# Protoboard_MX3-11-8.net
KiCad netlist of a schematic drawn in EAGLE
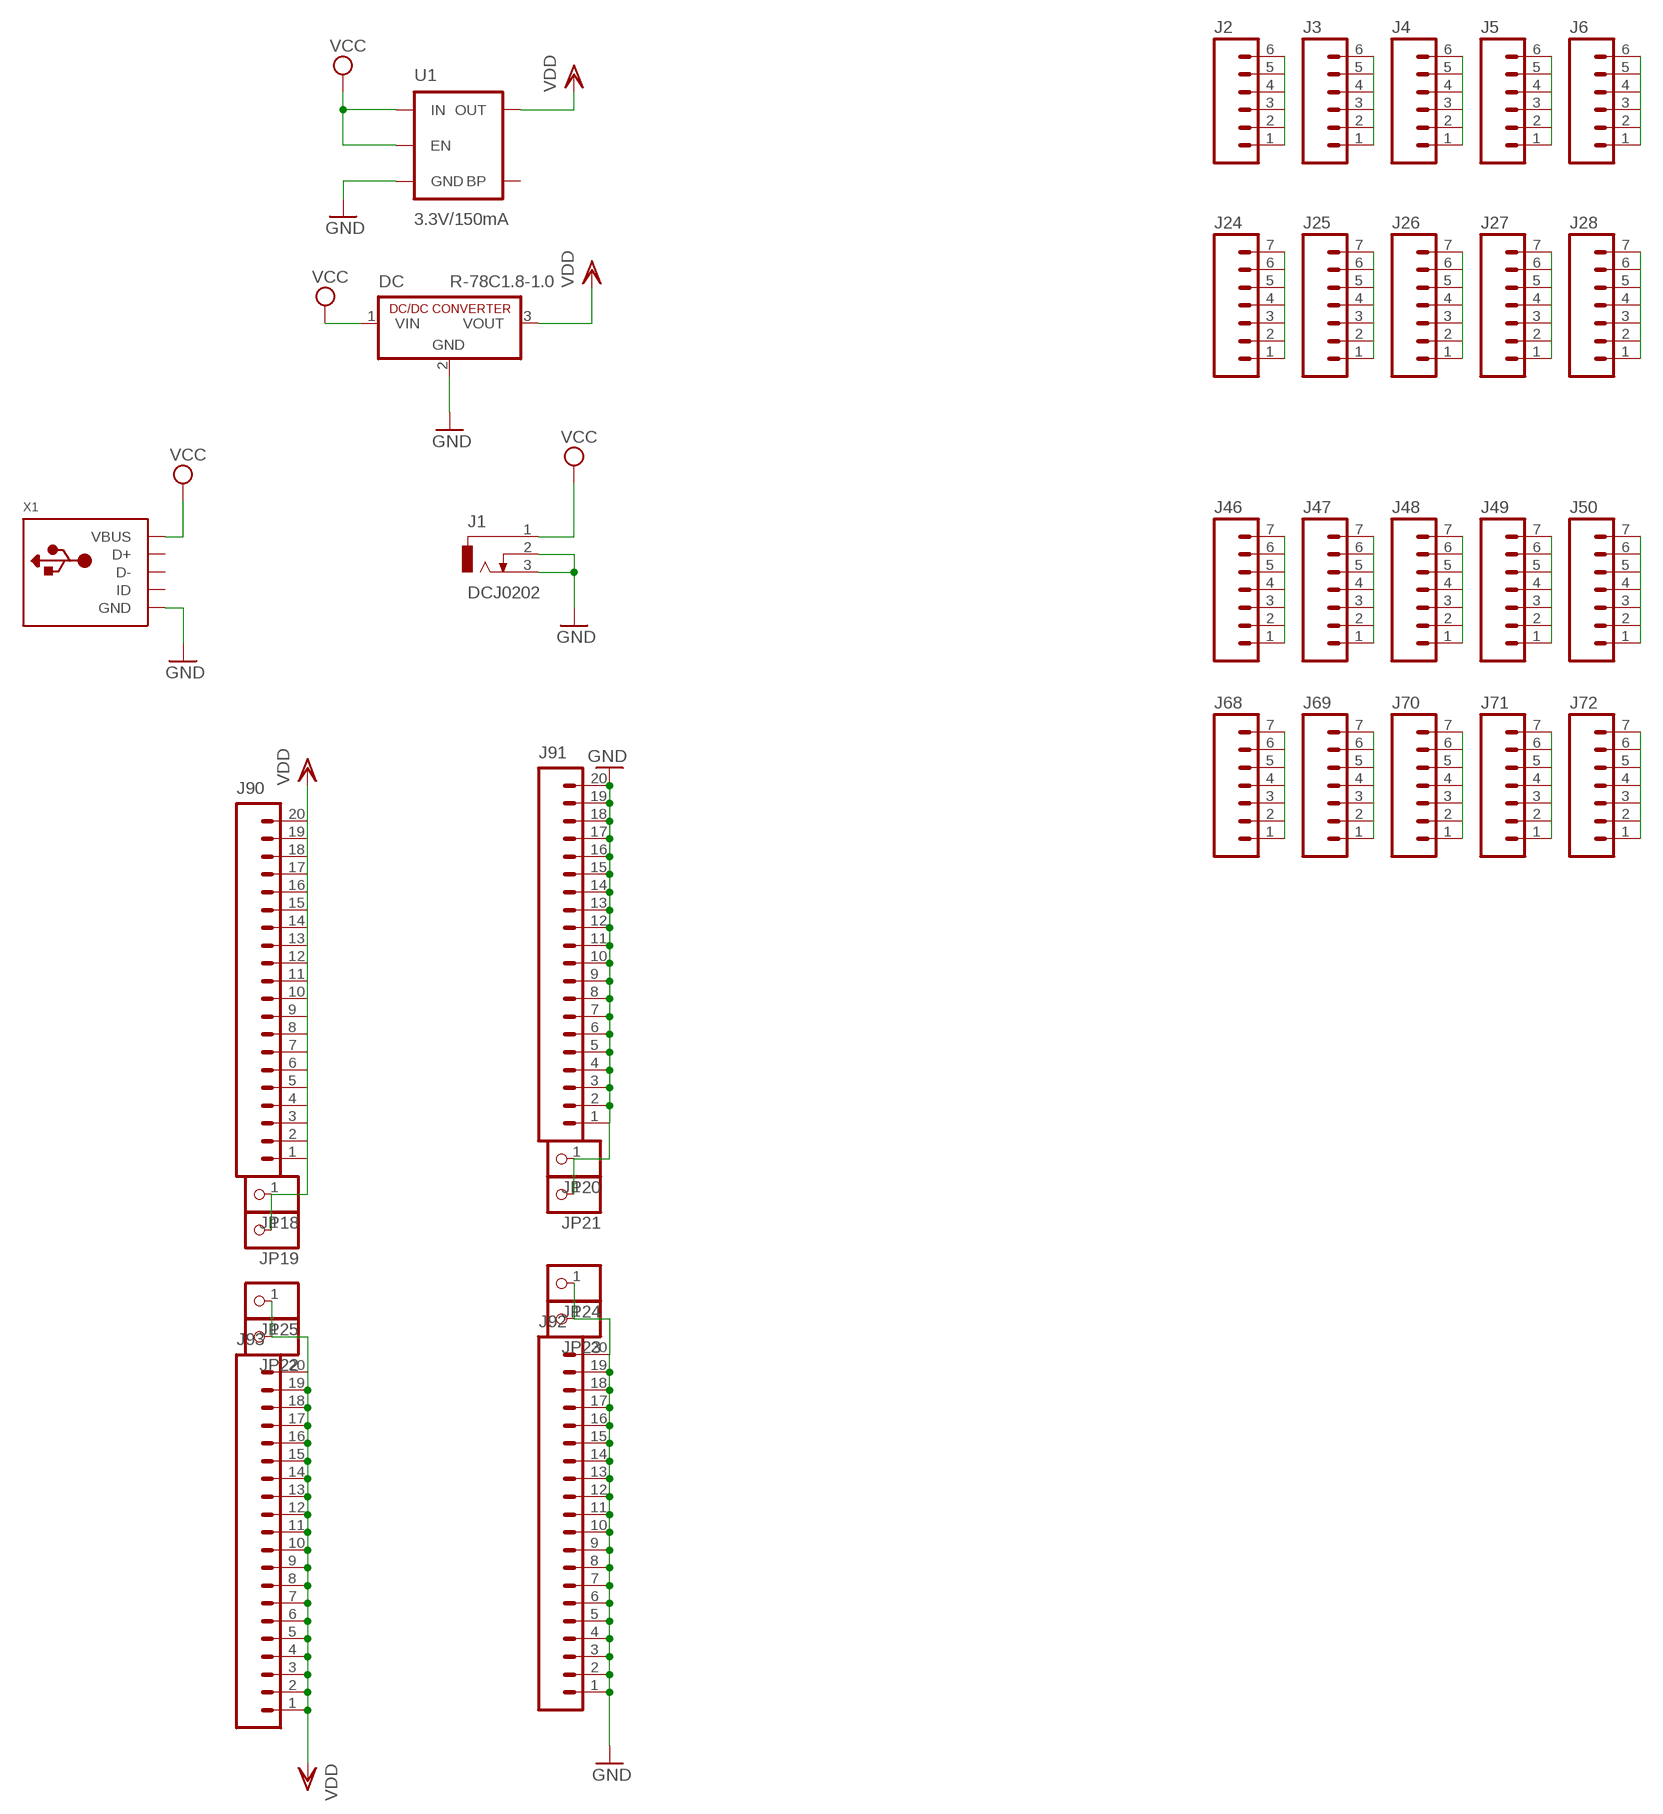
[diagram p0: schematic, sheet 1, part 1 of 2]
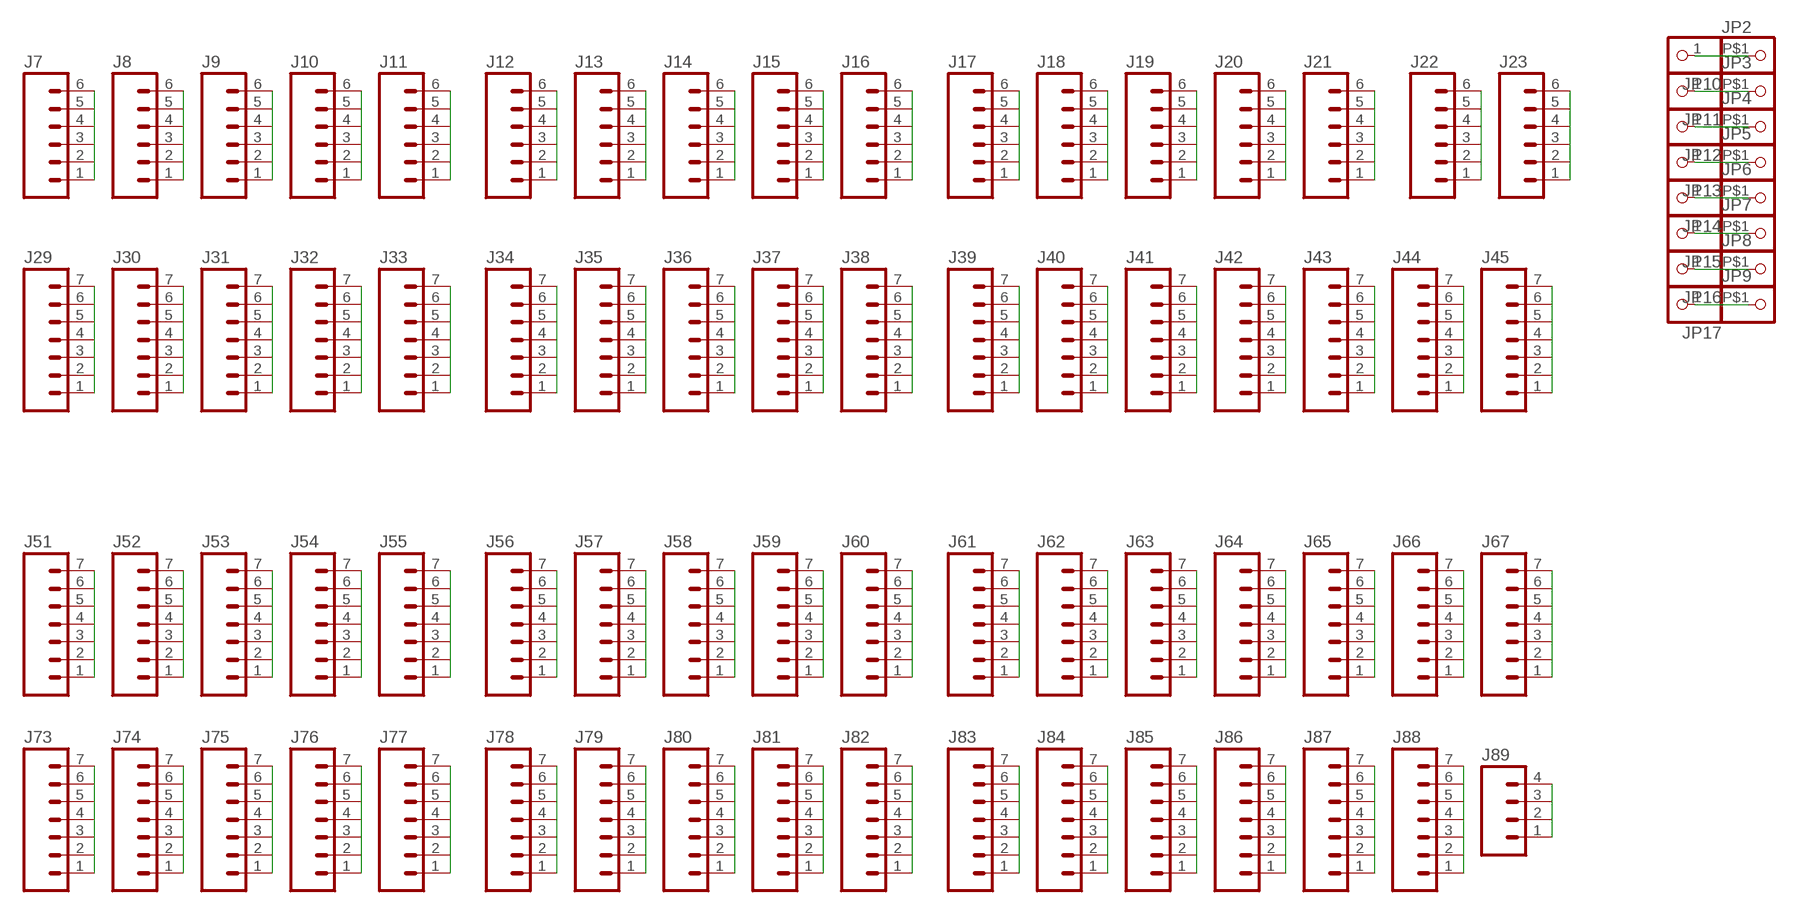
[diagram p1: schematic, sheet 1, part 2 of 2]

(export (version "E")
  (design (tool "Eeschema 10.0.6"))
  (components
    (comp (ref "DC")
      (value "R-78C1.8-1.0")
      (footprint "eagle-import:SIP3")
      (libsource (lib "eagle-import") (part "R-78C-1.01.8"))
    )
    (comp (ref "J1")
      (value "DCJ0202")
      (footprint "eagle-import:DCJ0202")
      (libsource (lib "eagle-import") (part "DCJ0202"))
    )
    (comp (ref "J2")
      (value "M06NO_SILK_FEMALE_PTH")
      (footprint "eagle-import:1X06_NO_SILK")
      (libsource (lib "eagle-import") (part "M06NO_SILK_FEMALE_PTH"))
    )
    (comp (ref "J3")
      (value "M06NO_SILK_FEMALE_PTH")
      (footprint "eagle-import:1X06_NO_SILK")
      (libsource (lib "eagle-import") (part "M06NO_SILK_FEMALE_PTH"))
    )
    (comp (ref "J4")
      (value "M06NO_SILK_FEMALE_PTH")
      (footprint "eagle-import:1X06_NO_SILK")
      (libsource (lib "eagle-import") (part "M06NO_SILK_FEMALE_PTH"))
    )
    (comp (ref "J5")
      (value "M06NO_SILK_FEMALE_PTH")
      (footprint "eagle-import:1X06_NO_SILK")
      (libsource (lib "eagle-import") (part "M06NO_SILK_FEMALE_PTH"))
    )
    (comp (ref "J6")
      (value "M06NO_SILK_FEMALE_PTH")
      (footprint "eagle-import:1X06_NO_SILK")
      (libsource (lib "eagle-import") (part "M06NO_SILK_FEMALE_PTH"))
    )
    (comp (ref "J7")
      (value "M06NO_SILK_FEMALE_PTH")
      (footprint "eagle-import:1X06_NO_SILK")
      (libsource (lib "eagle-import") (part "M06NO_SILK_FEMALE_PTH"))
    )
    (comp (ref "J8")
      (value "M06NO_SILK_FEMALE_PTH")
      (footprint "eagle-import:1X06_NO_SILK")
      (libsource (lib "eagle-import") (part "M06NO_SILK_FEMALE_PTH"))
    )
    (comp (ref "J9")
      (value "M06NO_SILK_FEMALE_PTH")
      (footprint "eagle-import:1X06_NO_SILK")
      (libsource (lib "eagle-import") (part "M06NO_SILK_FEMALE_PTH"))
    )
    (comp (ref "J10")
      (value "M06NO_SILK_FEMALE_PTH")
      (footprint "eagle-import:1X06_NO_SILK")
      (libsource (lib "eagle-import") (part "M06NO_SILK_FEMALE_PTH"))
    )
    (comp (ref "J11")
      (value "M06NO_SILK_FEMALE_PTH")
      (footprint "eagle-import:1X06_NO_SILK")
      (libsource (lib "eagle-import") (part "M06NO_SILK_FEMALE_PTH"))
    )
    (comp (ref "J12")
      (value "M06NO_SILK_FEMALE_PTH")
      (footprint "eagle-import:1X06_NO_SILK")
      (libsource (lib "eagle-import") (part "M06NO_SILK_FEMALE_PTH"))
    )
    (comp (ref "J13")
      (value "M06NO_SILK_FEMALE_PTH")
      (footprint "eagle-import:1X06_NO_SILK")
      (libsource (lib "eagle-import") (part "M06NO_SILK_FEMALE_PTH"))
    )
    (comp (ref "J14")
      (value "M06NO_SILK_FEMALE_PTH")
      (footprint "eagle-import:1X06_NO_SILK")
      (libsource (lib "eagle-import") (part "M06NO_SILK_FEMALE_PTH"))
    )
    (comp (ref "J15")
      (value "M06NO_SILK_FEMALE_PTH")
      (footprint "eagle-import:1X06_NO_SILK")
      (libsource (lib "eagle-import") (part "M06NO_SILK_FEMALE_PTH"))
    )
    (comp (ref "J16")
      (value "M06NO_SILK_FEMALE_PTH")
      (footprint "eagle-import:1X06_NO_SILK")
      (libsource (lib "eagle-import") (part "M06NO_SILK_FEMALE_PTH"))
    )
    (comp (ref "J17")
      (value "M06NO_SILK_FEMALE_PTH")
      (footprint "eagle-import:1X06_NO_SILK")
      (libsource (lib "eagle-import") (part "M06NO_SILK_FEMALE_PTH"))
    )
    (comp (ref "J18")
      (value "M06NO_SILK_FEMALE_PTH")
      (footprint "eagle-import:1X06_NO_SILK")
      (libsource (lib "eagle-import") (part "M06NO_SILK_FEMALE_PTH"))
    )
    (comp (ref "J19")
      (value "M06NO_SILK_FEMALE_PTH")
      (footprint "eagle-import:1X06_NO_SILK")
      (libsource (lib "eagle-import") (part "M06NO_SILK_FEMALE_PTH"))
    )
    (comp (ref "J20")
      (value "M06NO_SILK_FEMALE_PTH")
      (footprint "eagle-import:1X06_NO_SILK")
      (libsource (lib "eagle-import") (part "M06NO_SILK_FEMALE_PTH"))
    )
    (comp (ref "J21")
      (value "M06NO_SILK_FEMALE_PTH")
      (footprint "eagle-import:1X06_NO_SILK")
      (libsource (lib "eagle-import") (part "M06NO_SILK_FEMALE_PTH"))
    )
    (comp (ref "J22")
      (value "M06NO_SILK_FEMALE_PTH")
      (footprint "eagle-import:1X06_NO_SILK")
      (libsource (lib "eagle-import") (part "M06NO_SILK_FEMALE_PTH"))
    )
    (comp (ref "J23")
      (value "M06NO_SILK_FEMALE_PTH")
      (footprint "eagle-import:1X06_NO_SILK")
      (libsource (lib "eagle-import") (part "M06NO_SILK_FEMALE_PTH"))
    )
    (comp (ref "J24")
      (value "M07NO_SILK")
      (footprint "eagle-import:1X07_NO_SILK")
      (libsource (lib "eagle-import") (part "M07NO_SILK"))
    )
    (comp (ref "J25")
      (value "M07NO_SILK")
      (footprint "eagle-import:1X07_NO_SILK")
      (libsource (lib "eagle-import") (part "M07NO_SILK"))
    )
    (comp (ref "J26")
      (value "M07NO_SILK")
      (footprint "eagle-import:1X07_NO_SILK")
      (libsource (lib "eagle-import") (part "M07NO_SILK"))
    )
    (comp (ref "J27")
      (value "M07NO_SILK")
      (footprint "eagle-import:1X07_NO_SILK")
      (libsource (lib "eagle-import") (part "M07NO_SILK"))
    )
    (comp (ref "J28")
      (value "M07NO_SILK")
      (footprint "eagle-import:1X07_NO_SILK")
      (libsource (lib "eagle-import") (part "M07NO_SILK"))
    )
    (comp (ref "J29")
      (value "M07NO_SILK")
      (footprint "eagle-import:1X07_NO_SILK")
      (libsource (lib "eagle-import") (part "M07NO_SILK"))
    )
    (comp (ref "J30")
      (value "M07NO_SILK")
      (footprint "eagle-import:1X07_NO_SILK")
      (libsource (lib "eagle-import") (part "M07NO_SILK"))
    )
    (comp (ref "J31")
      (value "M07NO_SILK")
      (footprint "eagle-import:1X07_NO_SILK")
      (libsource (lib "eagle-import") (part "M07NO_SILK"))
    )
    (comp (ref "J32")
      (value "M07NO_SILK")
      (footprint "eagle-import:1X07_NO_SILK")
      (libsource (lib "eagle-import") (part "M07NO_SILK"))
    )
    (comp (ref "J33")
      (value "M07NO_SILK")
      (footprint "eagle-import:1X07_NO_SILK")
      (libsource (lib "eagle-import") (part "M07NO_SILK"))
    )
    (comp (ref "J34")
      (value "M07NO_SILK")
      (footprint "eagle-import:1X07_NO_SILK")
      (libsource (lib "eagle-import") (part "M07NO_SILK"))
    )
    (comp (ref "J35")
      (value "M07NO_SILK")
      (footprint "eagle-import:1X07_NO_SILK")
      (libsource (lib "eagle-import") (part "M07NO_SILK"))
    )
    (comp (ref "J36")
      (value "M07NO_SILK")
      (footprint "eagle-import:1X07_NO_SILK")
      (libsource (lib "eagle-import") (part "M07NO_SILK"))
    )
    (comp (ref "J37")
      (value "M07NO_SILK")
      (footprint "eagle-import:1X07_NO_SILK")
      (libsource (lib "eagle-import") (part "M07NO_SILK"))
    )
    (comp (ref "J38")
      (value "M07NO_SILK")
      (footprint "eagle-import:1X07_NO_SILK")
      (libsource (lib "eagle-import") (part "M07NO_SILK"))
    )
    (comp (ref "J39")
      (value "M07NO_SILK")
      (footprint "eagle-import:1X07_NO_SILK")
      (libsource (lib "eagle-import") (part "M07NO_SILK"))
    )
    (comp (ref "J40")
      (value "M07NO_SILK")
      (footprint "eagle-import:1X07_NO_SILK")
      (libsource (lib "eagle-import") (part "M07NO_SILK"))
    )
    (comp (ref "J41")
      (value "M07NO_SILK")
      (footprint "eagle-import:1X07_NO_SILK")
      (libsource (lib "eagle-import") (part "M07NO_SILK"))
    )
    (comp (ref "J42")
      (value "M07NO_SILK")
      (footprint "eagle-import:1X07_NO_SILK")
      (libsource (lib "eagle-import") (part "M07NO_SILK"))
    )
    (comp (ref "J43")
      (value "M07NO_SILK")
      (footprint "eagle-import:1X07_NO_SILK")
      (libsource (lib "eagle-import") (part "M07NO_SILK"))
    )
    (comp (ref "J44")
      (value "M07NO_SILK")
      (footprint "eagle-import:1X07_NO_SILK")
      (libsource (lib "eagle-import") (part "M07NO_SILK"))
    )
    (comp (ref "J45")
      (value "M07NO_SILK")
      (footprint "eagle-import:1X07_NO_SILK")
      (libsource (lib "eagle-import") (part "M07NO_SILK"))
    )
    (comp (ref "J46")
      (value "M07NO_SILK")
      (footprint "eagle-import:1X07_NO_SILK")
      (libsource (lib "eagle-import") (part "M07NO_SILK"))
    )
    (comp (ref "J47")
      (value "M07NO_SILK")
      (footprint "eagle-import:1X07_NO_SILK")
      (libsource (lib "eagle-import") (part "M07NO_SILK"))
    )
    (comp (ref "J48")
      (value "M07NO_SILK")
      (footprint "eagle-import:1X07_NO_SILK")
      (libsource (lib "eagle-import") (part "M07NO_SILK"))
    )
    (comp (ref "J49")
      (value "M07NO_SILK")
      (footprint "eagle-import:1X07_NO_SILK")
      (libsource (lib "eagle-import") (part "M07NO_SILK"))
    )
    (comp (ref "J50")
      (value "M07NO_SILK")
      (footprint "eagle-import:1X07_NO_SILK")
      (libsource (lib "eagle-import") (part "M07NO_SILK"))
    )
    (comp (ref "J51")
      (value "M07NO_SILK")
      (footprint "eagle-import:1X07_NO_SILK")
      (libsource (lib "eagle-import") (part "M07NO_SILK"))
    )
    (comp (ref "J52")
      (value "M07NO_SILK")
      (footprint "eagle-import:1X07_NO_SILK")
      (libsource (lib "eagle-import") (part "M07NO_SILK"))
    )
    (comp (ref "J53")
      (value "M07NO_SILK")
      (footprint "eagle-import:1X07_NO_SILK")
      (libsource (lib "eagle-import") (part "M07NO_SILK"))
    )
    (comp (ref "J54")
      (value "M07NO_SILK")
      (footprint "eagle-import:1X07_NO_SILK")
      (libsource (lib "eagle-import") (part "M07NO_SILK"))
    )
    (comp (ref "J55")
      (value "M07NO_SILK")
      (footprint "eagle-import:1X07_NO_SILK")
      (libsource (lib "eagle-import") (part "M07NO_SILK"))
    )
    (comp (ref "J56")
      (value "M07NO_SILK")
      (footprint "eagle-import:1X07_NO_SILK")
      (libsource (lib "eagle-import") (part "M07NO_SILK"))
    )
    (comp (ref "J57")
      (value "M07NO_SILK")
      (footprint "eagle-import:1X07_NO_SILK")
      (libsource (lib "eagle-import") (part "M07NO_SILK"))
    )
    (comp (ref "J58")
      (value "M07NO_SILK")
      (footprint "eagle-import:1X07_NO_SILK")
      (libsource (lib "eagle-import") (part "M07NO_SILK"))
    )
    (comp (ref "J59")
      (value "M07NO_SILK")
      (footprint "eagle-import:1X07_NO_SILK")
      (libsource (lib "eagle-import") (part "M07NO_SILK"))
    )
    (comp (ref "J60")
      (value "M07NO_SILK")
      (footprint "eagle-import:1X07_NO_SILK")
      (libsource (lib "eagle-import") (part "M07NO_SILK"))
    )
    (comp (ref "J61")
      (value "M07NO_SILK")
      (footprint "eagle-import:1X07_NO_SILK")
      (libsource (lib "eagle-import") (part "M07NO_SILK"))
    )
    (comp (ref "J62")
      (value "M07NO_SILK")
      (footprint "eagle-import:1X07_NO_SILK")
      (libsource (lib "eagle-import") (part "M07NO_SILK"))
    )
    (comp (ref "J63")
      (value "M07NO_SILK")
      (footprint "eagle-import:1X07_NO_SILK")
      (libsource (lib "eagle-import") (part "M07NO_SILK"))
    )
    (comp (ref "J64")
      (value "M07NO_SILK")
      (footprint "eagle-import:1X07_NO_SILK")
      (libsource (lib "eagle-import") (part "M07NO_SILK"))
    )
    (comp (ref "J65")
      (value "M07NO_SILK")
      (footprint "eagle-import:1X07_NO_SILK")
      (libsource (lib "eagle-import") (part "M07NO_SILK"))
    )
    (comp (ref "J66")
      (value "M07NO_SILK")
      (footprint "eagle-import:1X07_NO_SILK")
      (libsource (lib "eagle-import") (part "M07NO_SILK"))
    )
    (comp (ref "J67")
      (value "M07NO_SILK")
      (footprint "eagle-import:1X07_NO_SILK")
      (libsource (lib "eagle-import") (part "M07NO_SILK"))
    )
    (comp (ref "J68")
      (value "M07NO_SILK")
      (footprint "eagle-import:1X07_NO_SILK")
      (libsource (lib "eagle-import") (part "M07NO_SILK"))
    )
    (comp (ref "J69")
      (value "M07NO_SILK")
      (footprint "eagle-import:1X07_NO_SILK")
      (libsource (lib "eagle-import") (part "M07NO_SILK"))
    )
    (comp (ref "J70")
      (value "M07NO_SILK")
      (footprint "eagle-import:1X07_NO_SILK")
      (libsource (lib "eagle-import") (part "M07NO_SILK"))
    )
    (comp (ref "J71")
      (value "M07NO_SILK")
      (footprint "eagle-import:1X07_NO_SILK")
      (libsource (lib "eagle-import") (part "M07NO_SILK"))
    )
    (comp (ref "J72")
      (value "M07NO_SILK")
      (footprint "eagle-import:1X07_NO_SILK")
      (libsource (lib "eagle-import") (part "M07NO_SILK"))
    )
    (comp (ref "J73")
      (value "M07NO_SILK")
      (footprint "eagle-import:1X07_NO_SILK")
      (libsource (lib "eagle-import") (part "M07NO_SILK"))
    )
    (comp (ref "J74")
      (value "M07NO_SILK")
      (footprint "eagle-import:1X07_NO_SILK")
      (libsource (lib "eagle-import") (part "M07NO_SILK"))
    )
    (comp (ref "J75")
      (value "M07NO_SILK")
      (footprint "eagle-import:1X07_NO_SILK")
      (libsource (lib "eagle-import") (part "M07NO_SILK"))
    )
    (comp (ref "J76")
      (value "M07NO_SILK")
      (footprint "eagle-import:1X07_NO_SILK")
      (libsource (lib "eagle-import") (part "M07NO_SILK"))
    )
    (comp (ref "J77")
      (value "M07NO_SILK")
      (footprint "eagle-import:1X07_NO_SILK")
      (libsource (lib "eagle-import") (part "M07NO_SILK"))
    )
    (comp (ref "J78")
      (value "M07NO_SILK")
      (footprint "eagle-import:1X07_NO_SILK")
      (libsource (lib "eagle-import") (part "M07NO_SILK"))
    )
    (comp (ref "J79")
      (value "M07NO_SILK")
      (footprint "eagle-import:1X07_NO_SILK")
      (libsource (lib "eagle-import") (part "M07NO_SILK"))
    )
    (comp (ref "J80")
      (value "M07NO_SILK")
      (footprint "eagle-import:1X07_NO_SILK")
      (libsource (lib "eagle-import") (part "M07NO_SILK"))
    )
    (comp (ref "J81")
      (value "M07NO_SILK")
      (footprint "eagle-import:1X07_NO_SILK")
      (libsource (lib "eagle-import") (part "M07NO_SILK"))
    )
    (comp (ref "J82")
      (value "M07NO_SILK")
      (footprint "eagle-import:1X07_NO_SILK")
      (libsource (lib "eagle-import") (part "M07NO_SILK"))
    )
    (comp (ref "J83")
      (value "M07NO_SILK")
      (footprint "eagle-import:1X07_NO_SILK")
      (libsource (lib "eagle-import") (part "M07NO_SILK"))
    )
    (comp (ref "J84")
      (value "M07NO_SILK")
      (footprint "eagle-import:1X07_NO_SILK")
      (libsource (lib "eagle-import") (part "M07NO_SILK"))
    )
    (comp (ref "J85")
      (value "M07NO_SILK")
      (footprint "eagle-import:1X07_NO_SILK")
      (libsource (lib "eagle-import") (part "M07NO_SILK"))
    )
    (comp (ref "J86")
      (value "M07NO_SILK")
      (footprint "eagle-import:1X07_NO_SILK")
      (libsource (lib "eagle-import") (part "M07NO_SILK"))
    )
    (comp (ref "J87")
      (value "M07NO_SILK")
      (footprint "eagle-import:1X07_NO_SILK")
      (libsource (lib "eagle-import") (part "M07NO_SILK"))
    )
    (comp (ref "J88")
      (value "M07NO_SILK")
      (footprint "eagle-import:1X07_NO_SILK")
      (libsource (lib "eagle-import") (part "M07NO_SILK"))
    )
    (comp (ref "J89")
      (value "M04NO_SILK_ALL_ROUND")
      (footprint "eagle-import:1X04_NO_SILK_ALL_ROUND")
      (libsource (lib "eagle-import") (part "M04NO_SILK_ALL_ROUND"))
    )
    (comp (ref "J90")
      (value "M20NO_SILK_KIT")
      (footprint "eagle-import:1X20_NO_SILK_KIT")
      (libsource (lib "eagle-import") (part "M20NO_SILK_KIT"))
    )
    (comp (ref "J91")
      (value "M20NO_SILK_KIT")
      (footprint "eagle-import:1X20_NO_SILK_KIT")
      (libsource (lib "eagle-import") (part "M20NO_SILK_KIT"))
    )
    (comp (ref "J92")
      (value "M20NO_SILK_KIT")
      (footprint "eagle-import:1X20_NO_SILK_KIT")
      (libsource (lib "eagle-import") (part "M20NO_SILK_KIT"))
    )
    (comp (ref "J93")
      (value "M20NO_SILK_KIT")
      (footprint "eagle-import:1X20_NO_SILK_KIT")
      (libsource (lib "eagle-import") (part "M20NO_SILK_KIT"))
    )
    (comp (ref "JP2")
      (value "PINHD-1X1-BIGPOGO")
      (footprint "eagle-import:1X1-BIGPOGO")
      (libsource (lib "eagle-import") (part "PINHD-1X1-BIGPOGO"))
    )
    (comp (ref "JP3")
      (value "PINHD-1X1-BIGPOGO")
      (footprint "eagle-import:1X1-BIGPOGO")
      (libsource (lib "eagle-import") (part "PINHD-1X1-BIGPOGO"))
    )
    (comp (ref "JP4")
      (value "PINHD-1X1-BIGPOGO")
      (footprint "eagle-import:1X1-BIGPOGO")
      (libsource (lib "eagle-import") (part "PINHD-1X1-BIGPOGO"))
    )
    (comp (ref "JP5")
      (value "PINHD-1X1-BIGPOGO")
      (footprint "eagle-import:1X1-BIGPOGO")
      (libsource (lib "eagle-import") (part "PINHD-1X1-BIGPOGO"))
    )
    (comp (ref "JP6")
      (value "PINHD-1X1-BIGPOGO")
      (footprint "eagle-import:1X1-BIGPOGO")
      (libsource (lib "eagle-import") (part "PINHD-1X1-BIGPOGO"))
    )
    (comp (ref "JP7")
      (value "PINHD-1X1-BIGPOGO")
      (footprint "eagle-import:1X1-BIGPOGO")
      (libsource (lib "eagle-import") (part "PINHD-1X1-BIGPOGO"))
    )
    (comp (ref "JP8")
      (value "PINHD-1X1-BIGPOGO")
      (footprint "eagle-import:1X1-BIGPOGO")
      (libsource (lib "eagle-import") (part "PINHD-1X1-BIGPOGO"))
    )
    (comp (ref "JP9")
      (value "PINHD-1X1-BIGPOGO")
      (footprint "eagle-import:1X1-BIGPOGO")
      (libsource (lib "eagle-import") (part "PINHD-1X1-BIGPOGO"))
    )
    (comp (ref "JP10")
      (value "PINHD-1X1CB")
      (footprint "eagle-import:1X01-CLEANBIG")
      (libsource (lib "eagle-import") (part "PINHD-1X1CB"))
    )
    (comp (ref "JP11")
      (value "PINHD-1X1CB")
      (footprint "eagle-import:1X01-CLEANBIG")
      (libsource (lib "eagle-import") (part "PINHD-1X1CB"))
    )
    (comp (ref "JP12")
      (value "PINHD-1X1CB")
      (footprint "eagle-import:1X01-CLEANBIG")
      (libsource (lib "eagle-import") (part "PINHD-1X1CB"))
    )
    (comp (ref "JP13")
      (value "PINHD-1X1CB")
      (footprint "eagle-import:1X01-CLEANBIG")
      (libsource (lib "eagle-import") (part "PINHD-1X1CB"))
    )
    (comp (ref "JP14")
      (value "PINHD-1X1CB")
      (footprint "eagle-import:1X01-CLEANBIG")
      (libsource (lib "eagle-import") (part "PINHD-1X1CB"))
    )
    (comp (ref "JP15")
      (value "PINHD-1X1CB")
      (footprint "eagle-import:1X01-CLEANBIG")
      (libsource (lib "eagle-import") (part "PINHD-1X1CB"))
    )
    (comp (ref "JP16")
      (value "PINHD-1X1CB")
      (footprint "eagle-import:1X01-CLEANBIG")
      (libsource (lib "eagle-import") (part "PINHD-1X1CB"))
    )
    (comp (ref "JP17")
      (value "PINHD-1X1CB")
      (footprint "eagle-import:1X01-CLEANBIG")
      (libsource (lib "eagle-import") (part "PINHD-1X1CB"))
    )
    (comp (ref "JP18")
      (value "PINHD-1X1CB")
      (footprint "eagle-import:1X01-CLEANBIG")
      (libsource (lib "eagle-import") (part "PINHD-1X1CB"))
    )
    (comp (ref "JP19")
      (value "PINHD-1X1CB")
      (footprint "eagle-import:1X01-CLEANBIG")
      (libsource (lib "eagle-import") (part "PINHD-1X1CB"))
    )
    (comp (ref "JP20")
      (value "PINHD-1X1CB")
      (footprint "eagle-import:1X01-CLEANBIG")
      (libsource (lib "eagle-import") (part "PINHD-1X1CB"))
    )
    (comp (ref "JP21")
      (value "PINHD-1X1CB")
      (footprint "eagle-import:1X01-CLEANBIG")
      (libsource (lib "eagle-import") (part "PINHD-1X1CB"))
    )
    (comp (ref "JP22")
      (value "PINHD-1X1CB")
      (footprint "eagle-import:1X01-CLEANBIG")
      (libsource (lib "eagle-import") (part "PINHD-1X1CB"))
    )
    (comp (ref "JP23")
      (value "PINHD-1X1CB")
      (footprint "eagle-import:1X01-CLEANBIG")
      (libsource (lib "eagle-import") (part "PINHD-1X1CB"))
    )
    (comp (ref "JP24")
      (value "PINHD-1X1CB")
      (footprint "eagle-import:1X01-CLEANBIG")
      (libsource (lib "eagle-import") (part "PINHD-1X1CB"))
    )
    (comp (ref "JP25")
      (value "PINHD-1X1CB")
      (footprint "eagle-import:1X01-CLEANBIG")
      (libsource (lib "eagle-import") (part "PINHD-1X1CB"))
    )
    (comp (ref "U1")
      (value "3.3V/150mA")
      (footprint "eagle-import:SOT23-5")
      (libsource (lib "eagle-import") (part "V_REG_MIC52053.3V"))
    )
    (comp (ref "X1")
      (value "USBMICRO_20329")
      (footprint "eagle-import:4UCONN_20329")
      (libsource (lib "eagle-import") (part "USBMICRO_20329"))
    )
  )
  (nets
    (net (code "1") (name "GND") (class "Default")
      (node (ref "DC") (pin "2") (pinfunction "GND_2") (pintype "passive"))
      (node (ref "J1") (pin "2") (pinfunction "2_2") (pintype "passive"))
      (node (ref "J1") (pin "3") (pinfunction "3_3") (pintype "passive"))
      (node (ref "J91") (pin "1") (pinfunction "1_1") (pintype "passive"))
      (node (ref "J91") (pin "10") (pinfunction "10_10") (pintype "passive"))
      (node (ref "J91") (pin "11") (pinfunction "11_11") (pintype "passive"))
      (node (ref "J91") (pin "12") (pinfunction "12_12") (pintype "passive"))
      (node (ref "J91") (pin "13") (pinfunction "13_13") (pintype "passive"))
      (node (ref "J91") (pin "14") (pinfunction "14_14") (pintype "passive"))
      (node (ref "J91") (pin "15") (pinfunction "15_15") (pintype "passive"))
      (node (ref "J91") (pin "16") (pinfunction "16_16") (pintype "passive"))
      (node (ref "J91") (pin "17") (pinfunction "17_17") (pintype "passive"))
      (node (ref "J91") (pin "18") (pinfunction "18_18") (pintype "passive"))
      (node (ref "J91") (pin "19") (pinfunction "19_19") (pintype "passive"))
      (node (ref "J91") (pin "2") (pinfunction "2_2") (pintype "passive"))
      (node (ref "J91") (pin "20") (pinfunction "20_20") (pintype "passive"))
      (node (ref "J91") (pin "3") (pinfunction "3_3") (pintype "passive"))
      (node (ref "J91") (pin "4") (pinfunction "4_4") (pintype "passive"))
      (node (ref "J91") (pin "5") (pinfunction "5_5") (pintype "passive"))
      (node (ref "J91") (pin "6") (pinfunction "6_6") (pintype "passive"))
      (node (ref "J91") (pin "7") (pinfunction "7_7") (pintype "passive"))
      (node (ref "J91") (pin "8") (pinfunction "8_8") (pintype "passive"))
      (node (ref "J91") (pin "9") (pinfunction "9_9") (pintype "passive"))
      (node (ref "J92") (pin "1") (pinfunction "1_1") (pintype "passive"))
      (node (ref "J92") (pin "10") (pinfunction "10_10") (pintype "passive"))
      (node (ref "J92") (pin "11") (pinfunction "11_11") (pintype "passive"))
      (node (ref "J92") (pin "12") (pinfunction "12_12") (pintype "passive"))
      (node (ref "J92") (pin "13") (pinfunction "13_13") (pintype "passive"))
      (node (ref "J92") (pin "14") (pinfunction "14_14") (pintype "passive"))
      (node (ref "J92") (pin "15") (pinfunction "15_15") (pintype "passive"))
      (node (ref "J92") (pin "16") (pinfunction "16_16") (pintype "passive"))
      (node (ref "J92") (pin "17") (pinfunction "17_17") (pintype "passive"))
      (node (ref "J92") (pin "18") (pinfunction "18_18") (pintype "passive"))
      (node (ref "J92") (pin "19") (pinfunction "19_19") (pintype "passive"))
      (node (ref "J92") (pin "2") (pinfunction "2_2") (pintype "passive"))
      (node (ref "J92") (pin "20") (pinfunction "20_20") (pintype "passive"))
      (node (ref "J92") (pin "3") (pinfunction "3_3") (pintype "passive"))
      (node (ref "J92") (pin "4") (pinfunction "4_4") (pintype "passive"))
      (node (ref "J92") (pin "5") (pinfunction "5_5") (pintype "passive"))
      (node (ref "J92") (pin "6") (pinfunction "6_6") (pintype "passive"))
      (node (ref "J92") (pin "7") (pinfunction "7_7") (pintype "passive"))
      (node (ref "J92") (pin "8") (pinfunction "8_8") (pintype "passive"))
      (node (ref "J92") (pin "9") (pinfunction "9_9") (pintype "passive"))
      (node (ref "JP20") (pin "1") (pinfunction "1_1") (pintype "passive"))
      (node (ref "JP21") (pin "1") (pinfunction "1_1") (pintype "passive"))
      (node (ref "JP23") (pin "1") (pinfunction "1_1") (pintype "passive"))
      (node (ref "JP24") (pin "1") (pinfunction "1_1") (pintype "passive"))
      (node (ref "U1") (pin "2") (pinfunction "GND_2") (pintype "input"))
      (node (ref "X1") (pin "BASE@1") (pinfunction "GND_BASE@1") (pintype "power_in"))
      (node (ref "X1") (pin "BASE@2") (pinfunction "GND_BASE@2") (pintype "power_in"))
      (node (ref "X1") (pin "GND") (pinfunction "GND_GND") (pintype "power_in"))
      (node (ref "X1") (pin "SPRT@1") (pinfunction "GND_SPRT@1") (pintype "power_in"))
      (node (ref "X1") (pin "SPRT@2") (pinfunction "GND_SPRT@2") (pintype "power_in"))
      (node (ref "X1") (pin "SPRT@3") (pinfunction "GND_SPRT@3") (pintype "power_in"))
      (node (ref "X1") (pin "SPRT@4") (pinfunction "GND_SPRT@4") (pintype "power_in"))
    )
    (net (code "2") (name "Net-(J2-Pad1)") (class "Default")
      (node (ref "J2") (pin "1") (pinfunction "1_1") (pintype "passive"))
      (node (ref "J2") (pin "2") (pinfunction "2_2") (pintype "passive"))
      (node (ref "J2") (pin "3") (pinfunction "3_3") (pintype "passive"))
      (node (ref "J2") (pin "4") (pinfunction "4_4") (pintype "passive"))
      (node (ref "J2") (pin "5") (pinfunction "5_5") (pintype "passive"))
      (node (ref "J2") (pin "6") (pinfunction "6_6") (pintype "passive"))
    )
    (net (code "3") (name "Net-(J3-Pad1)") (class "Default")
      (node (ref "J3") (pin "1") (pinfunction "1_1") (pintype "passive"))
      (node (ref "J3") (pin "2") (pinfunction "2_2") (pintype "passive"))
      (node (ref "J3") (pin "3") (pinfunction "3_3") (pintype "passive"))
      (node (ref "J3") (pin "4") (pinfunction "4_4") (pintype "passive"))
      (node (ref "J3") (pin "5") (pinfunction "5_5") (pintype "passive"))
      (node (ref "J3") (pin "6") (pinfunction "6_6") (pintype "passive"))
    )
    (net (code "4") (name "Net-(J4-Pad1)") (class "Default")
      (node (ref "J4") (pin "1") (pinfunction "1_1") (pintype "passive"))
      (node (ref "J4") (pin "2") (pinfunction "2_2") (pintype "passive"))
      (node (ref "J4") (pin "3") (pinfunction "3_3") (pintype "passive"))
      (node (ref "J4") (pin "4") (pinfunction "4_4") (pintype "passive"))
      (node (ref "J4") (pin "5") (pinfunction "5_5") (pintype "passive"))
      (node (ref "J4") (pin "6") (pinfunction "6_6") (pintype "passive"))
    )
    (net (code "5") (name "Net-(J5-Pad1)") (class "Default")
      (node (ref "J5") (pin "1") (pinfunction "1_1") (pintype "passive"))
      (node (ref "J5") (pin "2") (pinfunction "2_2") (pintype "passive"))
      (node (ref "J5") (pin "3") (pinfunction "3_3") (pintype "passive"))
      (node (ref "J5") (pin "4") (pinfunction "4_4") (pintype "passive"))
      (node (ref "J5") (pin "5") (pinfunction "5_5") (pintype "passive"))
      (node (ref "J5") (pin "6") (pinfunction "6_6") (pintype "passive"))
    )
    (net (code "6") (name "Net-(J6-Pad1)") (class "Default")
      (node (ref "J6") (pin "1") (pinfunction "1_1") (pintype "passive"))
      (node (ref "J6") (pin "2") (pinfunction "2_2") (pintype "passive"))
      (node (ref "J6") (pin "3") (pinfunction "3_3") (pintype "passive"))
      (node (ref "J6") (pin "4") (pinfunction "4_4") (pintype "passive"))
      (node (ref "J6") (pin "5") (pinfunction "5_5") (pintype "passive"))
      (node (ref "J6") (pin "6") (pinfunction "6_6") (pintype "passive"))
    )
    (net (code "7") (name "Net-(J7-Pad1)") (class "Default")
      (node (ref "J7") (pin "1") (pinfunction "1_1") (pintype "passive"))
      (node (ref "J7") (pin "2") (pinfunction "2_2") (pintype "passive"))
      (node (ref "J7") (pin "3") (pinfunction "3_3") (pintype "passive"))
      (node (ref "J7") (pin "4") (pinfunction "4_4") (pintype "passive"))
      (node (ref "J7") (pin "5") (pinfunction "5_5") (pintype "passive"))
      (node (ref "J7") (pin "6") (pinfunction "6_6") (pintype "passive"))
    )
    (net (code "8") (name "Net-(J8-Pad1)") (class "Default")
      (node (ref "J8") (pin "1") (pinfunction "1_1") (pintype "passive"))
      (node (ref "J8") (pin "2") (pinfunction "2_2") (pintype "passive"))
      (node (ref "J8") (pin "3") (pinfunction "3_3") (pintype "passive"))
      (node (ref "J8") (pin "4") (pinfunction "4_4") (pintype "passive"))
      (node (ref "J8") (pin "5") (pinfunction "5_5") (pintype "passive"))
      (node (ref "J8") (pin "6") (pinfunction "6_6") (pintype "passive"))
    )
    (net (code "9") (name "Net-(J9-Pad1)") (class "Default")
      (node (ref "J9") (pin "1") (pinfunction "1_1") (pintype "passive"))
      (node (ref "J9") (pin "2") (pinfunction "2_2") (pintype "passive"))
      (node (ref "J9") (pin "3") (pinfunction "3_3") (pintype "passive"))
      (node (ref "J9") (pin "4") (pinfunction "4_4") (pintype "passive"))
      (node (ref "J9") (pin "5") (pinfunction "5_5") (pintype "passive"))
      (node (ref "J9") (pin "6") (pinfunction "6_6") (pintype "passive"))
    )
    (net (code "10") (name "Net-(J10-Pad1)") (class "Default")
      (node (ref "J10") (pin "1") (pinfunction "1_1") (pintype "passive"))
      (node (ref "J10") (pin "2") (pinfunction "2_2") (pintype "passive"))
      (node (ref "J10") (pin "3") (pinfunction "3_3") (pintype "passive"))
      (node (ref "J10") (pin "4") (pinfunction "4_4") (pintype "passive"))
      (node (ref "J10") (pin "5") (pinfunction "5_5") (pintype "passive"))
      (node (ref "J10") (pin "6") (pinfunction "6_6") (pintype "passive"))
    )
    (net (code "11") (name "Net-(J11-Pad1)") (class "Default")
      (node (ref "J11") (pin "1") (pinfunction "1_1") (pintype "passive"))
      (node (ref "J11") (pin "2") (pinfunction "2_2") (pintype "passive"))
      (node (ref "J11") (pin "3") (pinfunction "3_3") (pintype "passive"))
      (node (ref "J11") (pin "4") (pinfunction "4_4") (pintype "passive"))
      (node (ref "J11") (pin "5") (pinfunction "5_5") (pintype "passive"))
      (node (ref "J11") (pin "6") (pinfunction "6_6") (pintype "passive"))
    )
    (net (code "12") (name "Net-(J12-Pad1)") (class "Default")
      (node (ref "J12") (pin "1") (pinfunction "1_1") (pintype "passive"))
      (node (ref "J12") (pin "2") (pinfunction "2_2") (pintype "passive"))
      (node (ref "J12") (pin "3") (pinfunction "3_3") (pintype "passive"))
      (node (ref "J12") (pin "4") (pinfunction "4_4") (pintype "passive"))
      (node (ref "J12") (pin "5") (pinfunction "5_5") (pintype "passive"))
      (node (ref "J12") (pin "6") (pinfunction "6_6") (pintype "passive"))
    )
    (net (code "13") (name "Net-(J13-Pad1)") (class "Default")
      (node (ref "J13") (pin "1") (pinfunction "1_1") (pintype "passive"))
      (node (ref "J13") (pin "2") (pinfunction "2_2") (pintype "passive"))
      (node (ref "J13") (pin "3") (pinfunction "3_3") (pintype "passive"))
      (node (ref "J13") (pin "4") (pinfunction "4_4") (pintype "passive"))
      (node (ref "J13") (pin "5") (pinfunction "5_5") (pintype "passive"))
      (node (ref "J13") (pin "6") (pinfunction "6_6") (pintype "passive"))
    )
    (net (code "14") (name "Net-(J14-Pad1)") (class "Default")
      (node (ref "J14") (pin "1") (pinfunction "1_1") (pintype "passive"))
      (node (ref "J14") (pin "2") (pinfunction "2_2") (pintype "passive"))
      (node (ref "J14") (pin "3") (pinfunction "3_3") (pintype "passive"))
      (node (ref "J14") (pin "4") (pinfunction "4_4") (pintype "passive"))
      (node (ref "J14") (pin "5") (pinfunction "5_5") (pintype "passive"))
      (node (ref "J14") (pin "6") (pinfunction "6_6") (pintype "passive"))
    )
    (net (code "15") (name "Net-(J15-Pad1)") (class "Default")
      (node (ref "J15") (pin "1") (pinfunction "1_1") (pintype "passive"))
      (node (ref "J15") (pin "2") (pinfunction "2_2") (pintype "passive"))
      (node (ref "J15") (pin "3") (pinfunction "3_3") (pintype "passive"))
      (node (ref "J15") (pin "4") (pinfunction "4_4") (pintype "passive"))
      (node (ref "J15") (pin "5") (pinfunction "5_5") (pintype "passive"))
      (node (ref "J15") (pin "6") (pinfunction "6_6") (pintype "passive"))
    )
    (net (code "16") (name "Net-(J16-Pad1)") (class "Default")
      (node (ref "J16") (pin "1") (pinfunction "1_1") (pintype "passive"))
      (node (ref "J16") (pin "2") (pinfunction "2_2") (pintype "passive"))
      (node (ref "J16") (pin "3") (pinfunction "3_3") (pintype "passive"))
      (node (ref "J16") (pin "4") (pinfunction "4_4") (pintype "passive"))
      (node (ref "J16") (pin "5") (pinfunction "5_5") (pintype "passive"))
      (node (ref "J16") (pin "6") (pinfunction "6_6") (pintype "passive"))
    )
    (net (code "17") (name "Net-(J17-Pad1)") (class "Default")
      (node (ref "J17") (pin "1") (pinfunction "1_1") (pintype "passive"))
      (node (ref "J17") (pin "2") (pinfunction "2_2") (pintype "passive"))
      (node (ref "J17") (pin "3") (pinfunction "3_3") (pintype "passive"))
      (node (ref "J17") (pin "4") (pinfunction "4_4") (pintype "passive"))
      (node (ref "J17") (pin "5") (pinfunction "5_5") (pintype "passive"))
      (node (ref "J17") (pin "6") (pinfunction "6_6") (pintype "passive"))
    )
    (net (code "18") (name "Net-(J18-Pad1)") (class "Default")
      (node (ref "J18") (pin "1") (pinfunction "1_1") (pintype "passive"))
      (node (ref "J18") (pin "2") (pinfunction "2_2") (pintype "passive"))
      (node (ref "J18") (pin "3") (pinfunction "3_3") (pintype "passive"))
      (node (ref "J18") (pin "4") (pinfunction "4_4") (pintype "passive"))
      (node (ref "J18") (pin "5") (pinfunction "5_5") (pintype "passive"))
      (node (ref "J18") (pin "6") (pinfunction "6_6") (pintype "passive"))
    )
    (net (code "19") (name "Net-(J19-Pad1)") (class "Default")
      (node (ref "J19") (pin "1") (pinfunction "1_1") (pintype "passive"))
      (node (ref "J19") (pin "2") (pinfunction "2_2") (pintype "passive"))
      (node (ref "J19") (pin "3") (pinfunction "3_3") (pintype "passive"))
      (node (ref "J19") (pin "4") (pinfunction "4_4") (pintype "passive"))
      (node (ref "J19") (pin "5") (pinfunction "5_5") (pintype "passive"))
      (node (ref "J19") (pin "6") (pinfunction "6_6") (pintype "passive"))
    )
    (net (code "20") (name "Net-(J20-Pad1)") (class "Default")
      (node (ref "J20") (pin "1") (pinfunction "1_1") (pintype "passive"))
      (node (ref "J20") (pin "2") (pinfunction "2_2") (pintype "passive"))
      (node (ref "J20") (pin "3") (pinfunction "3_3") (pintype "passive"))
      (node (ref "J20") (pin "4") (pinfunction "4_4") (pintype "passive"))
      (node (ref "J20") (pin "5") (pinfunction "5_5") (pintype "passive"))
      (node (ref "J20") (pin "6") (pinfunction "6_6") (pintype "passive"))
    )
    (net (code "21") (name "Net-(J21-Pad1)") (class "Default")
      (node (ref "J21") (pin "1") (pinfunction "1_1") (pintype "passive"))
      (node (ref "J21") (pin "2") (pinfunction "2_2") (pintype "passive"))
      (node (ref "J21") (pin "3") (pinfunction "3_3") (pintype "passive"))
      (node (ref "J21") (pin "4") (pinfunction "4_4") (pintype "passive"))
      (node (ref "J21") (pin "5") (pinfunction "5_5") (pintype "passive"))
      (node (ref "J21") (pin "6") (pinfunction "6_6") (pintype "passive"))
    )
    (net (code "22") (name "Net-(J22-Pad1)") (class "Default")
      (node (ref "J22") (pin "1") (pinfunction "1_1") (pintype "passive"))
      (node (ref "J22") (pin "2") (pinfunction "2_2") (pintype "passive"))
      (node (ref "J22") (pin "3") (pinfunction "3_3") (pintype "passive"))
      (node (ref "J22") (pin "4") (pinfunction "4_4") (pintype "passive"))
      (node (ref "J22") (pin "5") (pinfunction "5_5") (pintype "passive"))
      (node (ref "J22") (pin "6") (pinfunction "6_6") (pintype "passive"))
    )
    (net (code "23") (name "Net-(J23-Pad1)") (class "Default")
      (node (ref "J23") (pin "1") (pinfunction "1_1") (pintype "passive"))
      (node (ref "J23") (pin "2") (pinfunction "2_2") (pintype "passive"))
      (node (ref "J23") (pin "3") (pinfunction "3_3") (pintype "passive"))
      (node (ref "J23") (pin "4") (pinfunction "4_4") (pintype "passive"))
      (node (ref "J23") (pin "5") (pinfunction "5_5") (pintype "passive"))
      (node (ref "J23") (pin "6") (pinfunction "6_6") (pintype "passive"))
    )
    (net (code "24") (name "Net-(J24-Pad1)") (class "Default")
      (node (ref "J24") (pin "1") (pinfunction "1_1") (pintype "passive"))
      (node (ref "J24") (pin "2") (pinfunction "2_2") (pintype "passive"))
      (node (ref "J24") (pin "3") (pinfunction "3_3") (pintype "passive"))
      (node (ref "J24") (pin "4") (pinfunction "4_4") (pintype "passive"))
      (node (ref "J24") (pin "5") (pinfunction "5_5") (pintype "passive"))
      (node (ref "J24") (pin "6") (pinfunction "6_6") (pintype "passive"))
      (node (ref "J24") (pin "7") (pinfunction "7_7") (pintype "passive"))
    )
    (net (code "25") (name "Net-(J25-Pad1)") (class "Default")
      (node (ref "J25") (pin "1") (pinfunction "1_1") (pintype "passive"))
      (node (ref "J25") (pin "2") (pinfunction "2_2") (pintype "passive"))
      (node (ref "J25") (pin "3") (pinfunction "3_3") (pintype "passive"))
      (node (ref "J25") (pin "4") (pinfunction "4_4") (pintype "passive"))
      (node (ref "J25") (pin "5") (pinfunction "5_5") (pintype "passive"))
      (node (ref "J25") (pin "6") (pinfunction "6_6") (pintype "passive"))
      (node (ref "J25") (pin "7") (pinfunction "7_7") (pintype "passive"))
    )
    (net (code "26") (name "Net-(J26-Pad1)") (class "Default")
      (node (ref "J26") (pin "1") (pinfunction "1_1") (pintype "passive"))
      (node (ref "J26") (pin "2") (pinfunction "2_2") (pintype "passive"))
      (node (ref "J26") (pin "3") (pinfunction "3_3") (pintype "passive"))
      (node (ref "J26") (pin "4") (pinfunction "4_4") (pintype "passive"))
      (node (ref "J26") (pin "5") (pinfunction "5_5") (pintype "passive"))
      (node (ref "J26") (pin "6") (pinfunction "6_6") (pintype "passive"))
      (node (ref "J26") (pin "7") (pinfunction "7_7") (pintype "passive"))
    )
    (net (code "27") (name "Net-(J27-Pad1)") (class "Default")
      (node (ref "J27") (pin "1") (pinfunction "1_1") (pintype "passive"))
      (node (ref "J27") (pin "2") (pinfunction "2_2") (pintype "passive"))
      (node (ref "J27") (pin "3") (pinfunction "3_3") (pintype "passive"))
      (node (ref "J27") (pin "4") (pinfunction "4_4") (pintype "passive"))
      (node (ref "J27") (pin "5") (pinfunction "5_5") (pintype "passive"))
      (node (ref "J27") (pin "6") (pinfunction "6_6") (pintype "passive"))
      (node (ref "J27") (pin "7") (pinfunction "7_7") (pintype "passive"))
    )
    (net (code "28") (name "Net-(J28-Pad1)") (class "Default")
      (node (ref "J28") (pin "1") (pinfunction "1_1") (pintype "passive"))
      (node (ref "J28") (pin "2") (pinfunction "2_2") (pintype "passive"))
      (node (ref "J28") (pin "3") (pinfunction "3_3") (pintype "passive"))
      (node (ref "J28") (pin "4") (pinfunction "4_4") (pintype "passive"))
      (node (ref "J28") (pin "5") (pinfunction "5_5") (pintype "passive"))
      (node (ref "J28") (pin "6") (pinfunction "6_6") (pintype "passive"))
      (node (ref "J28") (pin "7") (pinfunction "7_7") (pintype "passive"))
    )
    (net (code "29") (name "Net-(J29-Pad1)") (class "Default")
      (node (ref "J29") (pin "1") (pinfunction "1_1") (pintype "passive"))
      (node (ref "J29") (pin "2") (pinfunction "2_2") (pintype "passive"))
      (node (ref "J29") (pin "3") (pinfunction "3_3") (pintype "passive"))
      (node (ref "J29") (pin "4") (pinfunction "4_4") (pintype "passive"))
      (node (ref "J29") (pin "5") (pinfunction "5_5") (pintype "passive"))
      (node (ref "J29") (pin "6") (pinfunction "6_6") (pintype "passive"))
      (node (ref "J29") (pin "7") (pinfunction "7_7") (pintype "passive"))
    )
    (net (code "30") (name "Net-(J30-Pad1)") (class "Default")
      (node (ref "J30") (pin "1") (pinfunction "1_1") (pintype "passive"))
      (node (ref "J30") (pin "2") (pinfunction "2_2") (pintype "passive"))
      (node (ref "J30") (pin "3") (pinfunction "3_3") (pintype "passive"))
      (node (ref "J30") (pin "4") (pinfunction "4_4") (pintype "passive"))
      (node (ref "J30") (pin "5") (pinfunction "5_5") (pintype "passive"))
      (node (ref "J30") (pin "6") (pinfunction "6_6") (pintype "passive"))
      (node (ref "J30") (pin "7") (pinfunction "7_7") (pintype "passive"))
    )
    (net (code "31") (name "Net-(J31-Pad1)") (class "Default")
      (node (ref "J31") (pin "1") (pinfunction "1_1") (pintype "passive"))
      (node (ref "J31") (pin "2") (pinfunction "2_2") (pintype "passive"))
      (node (ref "J31") (pin "3") (pinfunction "3_3") (pintype "passive"))
      (node (ref "J31") (pin "4") (pinfunction "4_4") (pintype "passive"))
      (node (ref "J31") (pin "5") (pinfunction "5_5") (pintype "passive"))
      (node (ref "J31") (pin "6") (pinfunction "6_6") (pintype "passive"))
      (node (ref "J31") (pin "7") (pinfunction "7_7") (pintype "passive"))
    )
    (net (code "32") (name "Net-(J32-Pad1)") (class "Default")
      (node (ref "J32") (pin "1") (pinfunction "1_1") (pintype "passive"))
      (node (ref "J32") (pin "2") (pinfunction "2_2") (pintype "passive"))
      (node (ref "J32") (pin "3") (pinfunction "3_3") (pintype "passive"))
      (node (ref "J32") (pin "4") (pinfunction "4_4") (pintype "passive"))
      (node (ref "J32") (pin "5") (pinfunction "5_5") (pintype "passive"))
      (node (ref "J32") (pin "6") (pinfunction "6_6") (pintype "passive"))
      (node (ref "J32") (pin "7") (pinfunction "7_7") (pintype "passive"))
    )
    (net (code "33") (name "Net-(J33-Pad1)") (class "Default")
      (node (ref "J33") (pin "1") (pinfunction "1_1") (pintype "passive"))
      (node (ref "J33") (pin "2") (pinfunction "2_2") (pintype "passive"))
      (node (ref "J33") (pin "3") (pinfunction "3_3") (pintype "passive"))
      (node (ref "J33") (pin "4") (pinfunction "4_4") (pintype "passive"))
      (node (ref "J33") (pin "5") (pinfunction "5_5") (pintype "passive"))
      (node (ref "J33") (pin "6") (pinfunction "6_6") (pintype "passive"))
      (node (ref "J33") (pin "7") (pinfunction "7_7") (pintype "passive"))
    )
    (net (code "34") (name "Net-(J34-Pad1)") (class "Default")
      (node (ref "J34") (pin "1") (pinfunction "1_1") (pintype "passive"))
      (node (ref "J34") (pin "2") (pinfunction "2_2") (pintype "passive"))
      (node (ref "J34") (pin "3") (pinfunction "3_3") (pintype "passive"))
      (node (ref "J34") (pin "4") (pinfunction "4_4") (pintype "passive"))
      (node (ref "J34") (pin "5") (pinfunction "5_5") (pintype "passive"))
      (node (ref "J34") (pin "6") (pinfunction "6_6") (pintype "passive"))
      (node (ref "J34") (pin "7") (pinfunction "7_7") (pintype "passive"))
    )
    (net (code "35") (name "Net-(J35-Pad1)") (class "Default")
      (node (ref "J35") (pin "1") (pinfunction "1_1") (pintype "passive"))
      (node (ref "J35") (pin "2") (pinfunction "2_2") (pintype "passive"))
      (node (ref "J35") (pin "3") (pinfunction "3_3") (pintype "passive"))
      (node (ref "J35") (pin "4") (pinfunction "4_4") (pintype "passive"))
      (node (ref "J35") (pin "5") (pinfunction "5_5") (pintype "passive"))
      (node (ref "J35") (pin "6") (pinfunction "6_6") (pintype "passive"))
      (node (ref "J35") (pin "7") (pinfunction "7_7") (pintype "passive"))
    )
    (net (code "36") (name "Net-(J36-Pad1)") (class "Default")
      (node (ref "J36") (pin "1") (pinfunction "1_1") (pintype "passive"))
      (node (ref "J36") (pin "2") (pinfunction "2_2") (pintype "passive"))
      (node (ref "J36") (pin "3") (pinfunction "3_3") (pintype "passive"))
      (node (ref "J36") (pin "4") (pinfunction "4_4") (pintype "passive"))
      (node (ref "J36") (pin "5") (pinfunction "5_5") (pintype "passive"))
      (node (ref "J36") (pin "6") (pinfunction "6_6") (pintype "passive"))
      (node (ref "J36") (pin "7") (pinfunction "7_7") (pintype "passive"))
    )
    (net (code "37") (name "Net-(J37-Pad1)") (class "Default")
      (node (ref "J37") (pin "1") (pinfunction "1_1") (pintype "passive"))
      (node (ref "J37") (pin "2") (pinfunction "2_2") (pintype "passive"))
      (node (ref "J37") (pin "3") (pinfunction "3_3") (pintype "passive"))
      (node (ref "J37") (pin "4") (pinfunction "4_4") (pintype "passive"))
      (node (ref "J37") (pin "5") (pinfunction "5_5") (pintype "passive"))
      (node (ref "J37") (pin "6") (pinfunction "6_6") (pintype "passive"))
      (node (ref "J37") (pin "7") (pinfunction "7_7") (pintype "passive"))
    )
    (net (code "38") (name "Net-(J38-Pad1)") (class "Default")
      (node (ref "J38") (pin "1") (pinfunction "1_1") (pintype "passive"))
      (node (ref "J38") (pin "2") (pinfunction "2_2") (pintype "passive"))
      (node (ref "J38") (pin "3") (pinfunction "3_3") (pintype "passive"))
      (node (ref "J38") (pin "4") (pinfunction "4_4") (pintype "passive"))
      (node (ref "J38") (pin "5") (pinfunction "5_5") (pintype "passive"))
      (node (ref "J38") (pin "6") (pinfunction "6_6") (pintype "passive"))
      (node (ref "J38") (pin "7") (pinfunction "7_7") (pintype "passive"))
    )
    (net (code "39") (name "Net-(J39-Pad1)") (class "Default")
      (node (ref "J39") (pin "1") (pinfunction "1_1") (pintype "passive"))
      (node (ref "J39") (pin "2") (pinfunction "2_2") (pintype "passive"))
      (node (ref "J39") (pin "3") (pinfunction "3_3") (pintype "passive"))
      (node (ref "J39") (pin "4") (pinfunction "4_4") (pintype "passive"))
      (node (ref "J39") (pin "5") (pinfunction "5_5") (pintype "passive"))
      (node (ref "J39") (pin "6") (pinfunction "6_6") (pintype "passive"))
      (node (ref "J39") (pin "7") (pinfunction "7_7") (pintype "passive"))
    )
    (net (code "40") (name "Net-(J40-Pad1)") (class "Default")
      (node (ref "J40") (pin "1") (pinfunction "1_1") (pintype "passive"))
      (node (ref "J40") (pin "2") (pinfunction "2_2") (pintype "passive"))
      (node (ref "J40") (pin "3") (pinfunction "3_3") (pintype "passive"))
      (node (ref "J40") (pin "4") (pinfunction "4_4") (pintype "passive"))
      (node (ref "J40") (pin "5") (pinfunction "5_5") (pintype "passive"))
      (node (ref "J40") (pin "6") (pinfunction "6_6") (pintype "passive"))
      (node (ref "J40") (pin "7") (pinfunction "7_7") (pintype "passive"))
    )
    (net (code "41") (name "Net-(J41-Pad1)") (class "Default")
      (node (ref "J41") (pin "1") (pinfunction "1_1") (pintype "passive"))
      (node (ref "J41") (pin "2") (pinfunction "2_2") (pintype "passive"))
      (node (ref "J41") (pin "3") (pinfunction "3_3") (pintype "passive"))
      (node (ref "J41") (pin "4") (pinfunction "4_4") (pintype "passive"))
      (node (ref "J41") (pin "5") (pinfunction "5_5") (pintype "passive"))
      (node (ref "J41") (pin "6") (pinfunction "6_6") (pintype "passive"))
      (node (ref "J41") (pin "7") (pinfunction "7_7") (pintype "passive"))
    )
    (net (code "42") (name "Net-(J42-Pad1)") (class "Default")
      (node (ref "J42") (pin "1") (pinfunction "1_1") (pintype "passive"))
      (node (ref "J42") (pin "2") (pinfunction "2_2") (pintype "passive"))
      (node (ref "J42") (pin "3") (pinfunction "3_3") (pintype "passive"))
      (node (ref "J42") (pin "4") (pinfunction "4_4") (pintype "passive"))
      (node (ref "J42") (pin "5") (pinfunction "5_5") (pintype "passive"))
      (node (ref "J42") (pin "6") (pinfunction "6_6") (pintype "passive"))
      (node (ref "J42") (pin "7") (pinfunction "7_7") (pintype "passive"))
    )
    (net (code "43") (name "Net-(J43-Pad1)") (class "Default")
      (node (ref "J43") (pin "1") (pinfunction "1_1") (pintype "passive"))
      (node (ref "J43") (pin "2") (pinfunction "2_2") (pintype "passive"))
      (node (ref "J43") (pin "3") (pinfunction "3_3") (pintype "passive"))
      (node (ref "J43") (pin "4") (pinfunction "4_4") (pintype "passive"))
      (node (ref "J43") (pin "5") (pinfunction "5_5") (pintype "passive"))
      (node (ref "J43") (pin "6") (pinfunction "6_6") (pintype "passive"))
      (node (ref "J43") (pin "7") (pinfunction "7_7") (pintype "passive"))
    )
    (net (code "44") (name "Net-(J44-Pad1)") (class "Default")
      (node (ref "J44") (pin "1") (pinfunction "1_1") (pintype "passive"))
      (node (ref "J44") (pin "2") (pinfunction "2_2") (pintype "passive"))
      (node (ref "J44") (pin "3") (pinfunction "3_3") (pintype "passive"))
      (node (ref "J44") (pin "4") (pinfunction "4_4") (pintype "passive"))
      (node (ref "J44") (pin "5") (pinfunction "5_5") (pintype "passive"))
      (node (ref "J44") (pin "6") (pinfunction "6_6") (pintype "passive"))
      (node (ref "J44") (pin "7") (pinfunction "7_7") (pintype "passive"))
    )
    (net (code "45") (name "Net-(J45-Pad1)") (class "Default")
      (node (ref "J45") (pin "1") (pinfunction "1_1") (pintype "passive"))
      (node (ref "J45") (pin "2") (pinfunction "2_2") (pintype "passive"))
      (node (ref "J45") (pin "3") (pinfunction "3_3") (pintype "passive"))
      (node (ref "J45") (pin "4") (pinfunction "4_4") (pintype "passive"))
      (node (ref "J45") (pin "5") (pinfunction "5_5") (pintype "passive"))
      (node (ref "J45") (pin "6") (pinfunction "6_6") (pintype "passive"))
      (node (ref "J45") (pin "7") (pinfunction "7_7") (pintype "passive"))
    )
    (net (code "46") (name "Net-(J46-Pad1)") (class "Default")
      (node (ref "J46") (pin "1") (pinfunction "1_1") (pintype "passive"))
      (node (ref "J46") (pin "2") (pinfunction "2_2") (pintype "passive"))
      (node (ref "J46") (pin "3") (pinfunction "3_3") (pintype "passive"))
      (node (ref "J46") (pin "4") (pinfunction "4_4") (pintype "passive"))
      (node (ref "J46") (pin "5") (pinfunction "5_5") (pintype "passive"))
      (node (ref "J46") (pin "6") (pinfunction "6_6") (pintype "passive"))
      (node (ref "J46") (pin "7") (pinfunction "7_7") (pintype "passive"))
    )
    (net (code "47") (name "Net-(J47-Pad1)") (class "Default")
      (node (ref "J47") (pin "1") (pinfunction "1_1") (pintype "passive"))
      (node (ref "J47") (pin "2") (pinfunction "2_2") (pintype "passive"))
      (node (ref "J47") (pin "3") (pinfunction "3_3") (pintype "passive"))
      (node (ref "J47") (pin "4") (pinfunction "4_4") (pintype "passive"))
      (node (ref "J47") (pin "5") (pinfunction "5_5") (pintype "passive"))
      (node (ref "J47") (pin "6") (pinfunction "6_6") (pintype "passive"))
      (node (ref "J47") (pin "7") (pinfunction "7_7") (pintype "passive"))
    )
    (net (code "48") (name "Net-(J48-Pad1)") (class "Default")
      (node (ref "J48") (pin "1") (pinfunction "1_1") (pintype "passive"))
      (node (ref "J48") (pin "2") (pinfunction "2_2") (pintype "passive"))
      (node (ref "J48") (pin "3") (pinfunction "3_3") (pintype "passive"))
      (node (ref "J48") (pin "4") (pinfunction "4_4") (pintype "passive"))
      (node (ref "J48") (pin "5") (pinfunction "5_5") (pintype "passive"))
      (node (ref "J48") (pin "6") (pinfunction "6_6") (pintype "passive"))
      (node (ref "J48") (pin "7") (pinfunction "7_7") (pintype "passive"))
    )
    (net (code "49") (name "Net-(J49-Pad1)") (class "Default")
      (node (ref "J49") (pin "1") (pinfunction "1_1") (pintype "passive"))
      (node (ref "J49") (pin "2") (pinfunction "2_2") (pintype "passive"))
      (node (ref "J49") (pin "3") (pinfunction "3_3") (pintype "passive"))
      (node (ref "J49") (pin "4") (pinfunction "4_4") (pintype "passive"))
      (node (ref "J49") (pin "5") (pinfunction "5_5") (pintype "passive"))
      (node (ref "J49") (pin "6") (pinfunction "6_6") (pintype "passive"))
      (node (ref "J49") (pin "7") (pinfunction "7_7") (pintype "passive"))
    )
    (net (code "50") (name "Net-(J50-Pad1)") (class "Default")
      (node (ref "J50") (pin "1") (pinfunction "1_1") (pintype "passive"))
      (node (ref "J50") (pin "2") (pinfunction "2_2") (pintype "passive"))
      (node (ref "J50") (pin "3") (pinfunction "3_3") (pintype "passive"))
      (node (ref "J50") (pin "4") (pinfunction "4_4") (pintype "passive"))
      (node (ref "J50") (pin "5") (pinfunction "5_5") (pintype "passive"))
      (node (ref "J50") (pin "6") (pinfunction "6_6") (pintype "passive"))
      (node (ref "J50") (pin "7") (pinfunction "7_7") (pintype "passive"))
    )
    (net (code "51") (name "Net-(J51-Pad1)") (class "Default")
      (node (ref "J51") (pin "1") (pinfunction "1_1") (pintype "passive"))
      (node (ref "J51") (pin "2") (pinfunction "2_2") (pintype "passive"))
      (node (ref "J51") (pin "3") (pinfunction "3_3") (pintype "passive"))
      (node (ref "J51") (pin "4") (pinfunction "4_4") (pintype "passive"))
      (node (ref "J51") (pin "5") (pinfunction "5_5") (pintype "passive"))
      (node (ref "J51") (pin "6") (pinfunction "6_6") (pintype "passive"))
      (node (ref "J51") (pin "7") (pinfunction "7_7") (pintype "passive"))
    )
    (net (code "52") (name "Net-(J52-Pad1)") (class "Default")
      (node (ref "J52") (pin "1") (pinfunction "1_1") (pintype "passive"))
      (node (ref "J52") (pin "2") (pinfunction "2_2") (pintype "passive"))
      (node (ref "J52") (pin "3") (pinfunction "3_3") (pintype "passive"))
      (node (ref "J52") (pin "4") (pinfunction "4_4") (pintype "passive"))
      (node (ref "J52") (pin "5") (pinfunction "5_5") (pintype "passive"))
      (node (ref "J52") (pin "6") (pinfunction "6_6") (pintype "passive"))
      (node (ref "J52") (pin "7") (pinfunction "7_7") (pintype "passive"))
    )
    (net (code "53") (name "Net-(J53-Pad1)") (class "Default")
      (node (ref "J53") (pin "1") (pinfunction "1_1") (pintype "passive"))
      (node (ref "J53") (pin "2") (pinfunction "2_2") (pintype "passive"))
      (node (ref "J53") (pin "3") (pinfunction "3_3") (pintype "passive"))
      (node (ref "J53") (pin "4") (pinfunction "4_4") (pintype "passive"))
      (node (ref "J53") (pin "5") (pinfunction "5_5") (pintype "passive"))
      (node (ref "J53") (pin "6") (pinfunction "6_6") (pintype "passive"))
      (node (ref "J53") (pin "7") (pinfunction "7_7") (pintype "passive"))
    )
    (net (code "54") (name "Net-(J54-Pad1)") (class "Default")
      (node (ref "J54") (pin "1") (pinfunction "1_1") (pintype "passive"))
      (node (ref "J54") (pin "2") (pinfunction "2_2") (pintype "passive"))
      (node (ref "J54") (pin "3") (pinfunction "3_3") (pintype "passive"))
      (node (ref "J54") (pin "4") (pinfunction "4_4") (pintype "passive"))
      (node (ref "J54") (pin "5") (pinfunction "5_5") (pintype "passive"))
      (node (ref "J54") (pin "6") (pinfunction "6_6") (pintype "passive"))
      (node (ref "J54") (pin "7") (pinfunction "7_7") (pintype "passive"))
    )
    (net (code "55") (name "Net-(J55-Pad1)") (class "Default")
      (node (ref "J55") (pin "1") (pinfunction "1_1") (pintype "passive"))
      (node (ref "J55") (pin "2") (pinfunction "2_2") (pintype "passive"))
      (node (ref "J55") (pin "3") (pinfunction "3_3") (pintype "passive"))
      (node (ref "J55") (pin "4") (pinfunction "4_4") (pintype "passive"))
      (node (ref "J55") (pin "5") (pinfunction "5_5") (pintype "passive"))
      (node (ref "J55") (pin "6") (pinfunction "6_6") (pintype "passive"))
      (node (ref "J55") (pin "7") (pinfunction "7_7") (pintype "passive"))
    )
    (net (code "56") (name "Net-(J56-Pad1)") (class "Default")
      (node (ref "J56") (pin "1") (pinfunction "1_1") (pintype "passive"))
      (node (ref "J56") (pin "2") (pinfunction "2_2") (pintype "passive"))
      (node (ref "J56") (pin "3") (pinfunction "3_3") (pintype "passive"))
      (node (ref "J56") (pin "4") (pinfunction "4_4") (pintype "passive"))
      (node (ref "J56") (pin "5") (pinfunction "5_5") (pintype "passive"))
      (node (ref "J56") (pin "6") (pinfunction "6_6") (pintype "passive"))
      (node (ref "J56") (pin "7") (pinfunction "7_7") (pintype "passive"))
    )
    (net (code "57") (name "Net-(J57-Pad1)") (class "Default")
      (node (ref "J57") (pin "1") (pinfunction "1_1") (pintype "passive"))
      (node (ref "J57") (pin "2") (pinfunction "2_2") (pintype "passive"))
      (node (ref "J57") (pin "3") (pinfunction "3_3") (pintype "passive"))
      (node (ref "J57") (pin "4") (pinfunction "4_4") (pintype "passive"))
      (node (ref "J57") (pin "5") (pinfunction "5_5") (pintype "passive"))
      (node (ref "J57") (pin "6") (pinfunction "6_6") (pintype "passive"))
      (node (ref "J57") (pin "7") (pinfunction "7_7") (pintype "passive"))
    )
    (net (code "58") (name "Net-(J58-Pad1)") (class "Default")
      (node (ref "J58") (pin "1") (pinfunction "1_1") (pintype "passive"))
      (node (ref "J58") (pin "2") (pinfunction "2_2") (pintype "passive"))
      (node (ref "J58") (pin "3") (pinfunction "3_3") (pintype "passive"))
      (node (ref "J58") (pin "4") (pinfunction "4_4") (pintype "passive"))
      (node (ref "J58") (pin "5") (pinfunction "5_5") (pintype "passive"))
      (node (ref "J58") (pin "6") (pinfunction "6_6") (pintype "passive"))
      (node (ref "J58") (pin "7") (pinfunction "7_7") (pintype "passive"))
    )
    (net (code "59") (name "Net-(J59-Pad1)") (class "Default")
      (node (ref "J59") (pin "1") (pinfunction "1_1") (pintype "passive"))
      (node (ref "J59") (pin "2") (pinfunction "2_2") (pintype "passive"))
      (node (ref "J59") (pin "3") (pinfunction "3_3") (pintype "passive"))
      (node (ref "J59") (pin "4") (pinfunction "4_4") (pintype "passive"))
      (node (ref "J59") (pin "5") (pinfunction "5_5") (pintype "passive"))
      (node (ref "J59") (pin "6") (pinfunction "6_6") (pintype "passive"))
      (node (ref "J59") (pin "7") (pinfunction "7_7") (pintype "passive"))
    )
    (net (code "60") (name "Net-(J60-Pad1)") (class "Default")
      (node (ref "J60") (pin "1") (pinfunction "1_1") (pintype "passive"))
      (node (ref "J60") (pin "2") (pinfunction "2_2") (pintype "passive"))
      (node (ref "J60") (pin "3") (pinfunction "3_3") (pintype "passive"))
      (node (ref "J60") (pin "4") (pinfunction "4_4") (pintype "passive"))
      (node (ref "J60") (pin "5") (pinfunction "5_5") (pintype "passive"))
      (node (ref "J60") (pin "6") (pinfunction "6_6") (pintype "passive"))
      (node (ref "J60") (pin "7") (pinfunction "7_7") (pintype "passive"))
    )
    (net (code "61") (name "Net-(J61-Pad1)") (class "Default")
      (node (ref "J61") (pin "1") (pinfunction "1_1") (pintype "passive"))
      (node (ref "J61") (pin "2") (pinfunction "2_2") (pintype "passive"))
      (node (ref "J61") (pin "3") (pinfunction "3_3") (pintype "passive"))
      (node (ref "J61") (pin "4") (pinfunction "4_4") (pintype "passive"))
      (node (ref "J61") (pin "5") (pinfunction "5_5") (pintype "passive"))
      (node (ref "J61") (pin "6") (pinfunction "6_6") (pintype "passive"))
      (node (ref "J61") (pin "7") (pinfunction "7_7") (pintype "passive"))
    )
    (net (code "62") (name "Net-(J62-Pad1)") (class "Default")
      (node (ref "J62") (pin "1") (pinfunction "1_1") (pintype "passive"))
      (node (ref "J62") (pin "2") (pinfunction "2_2") (pintype "passive"))
      (node (ref "J62") (pin "3") (pinfunction "3_3") (pintype "passive"))
      (node (ref "J62") (pin "4") (pinfunction "4_4") (pintype "passive"))
      (node (ref "J62") (pin "5") (pinfunction "5_5") (pintype "passive"))
      (node (ref "J62") (pin "6") (pinfunction "6_6") (pintype "passive"))
      (node (ref "J62") (pin "7") (pinfunction "7_7") (pintype "passive"))
    )
    (net (code "63") (name "Net-(J63-Pad1)") (class "Default")
      (node (ref "J63") (pin "1") (pinfunction "1_1") (pintype "passive"))
      (node (ref "J63") (pin "2") (pinfunction "2_2") (pintype "passive"))
      (node (ref "J63") (pin "3") (pinfunction "3_3") (pintype "passive"))
      (node (ref "J63") (pin "4") (pinfunction "4_4") (pintype "passive"))
      (node (ref "J63") (pin "5") (pinfunction "5_5") (pintype "passive"))
      (node (ref "J63") (pin "6") (pinfunction "6_6") (pintype "passive"))
      (node (ref "J63") (pin "7") (pinfunction "7_7") (pintype "passive"))
    )
    (net (code "64") (name "Net-(J64-Pad1)") (class "Default")
      (node (ref "J64") (pin "1") (pinfunction "1_1") (pintype "passive"))
      (node (ref "J64") (pin "2") (pinfunction "2_2") (pintype "passive"))
      (node (ref "J64") (pin "3") (pinfunction "3_3") (pintype "passive"))
      (node (ref "J64") (pin "4") (pinfunction "4_4") (pintype "passive"))
      (node (ref "J64") (pin "5") (pinfunction "5_5") (pintype "passive"))
      (node (ref "J64") (pin "6") (pinfunction "6_6") (pintype "passive"))
      (node (ref "J64") (pin "7") (pinfunction "7_7") (pintype "passive"))
    )
    (net (code "65") (name "Net-(J65-Pad1)") (class "Default")
      (node (ref "J65") (pin "1") (pinfunction "1_1") (pintype "passive"))
      (node (ref "J65") (pin "2") (pinfunction "2_2") (pintype "passive"))
      (node (ref "J65") (pin "3") (pinfunction "3_3") (pintype "passive"))
      (node (ref "J65") (pin "4") (pinfunction "4_4") (pintype "passive"))
      (node (ref "J65") (pin "5") (pinfunction "5_5") (pintype "passive"))
      (node (ref "J65") (pin "6") (pinfunction "6_6") (pintype "passive"))
      (node (ref "J65") (pin "7") (pinfunction "7_7") (pintype "passive"))
    )
    (net (code "66") (name "Net-(J66-Pad1)") (class "Default")
      (node (ref "J66") (pin "1") (pinfunction "1_1") (pintype "passive"))
      (node (ref "J66") (pin "2") (pinfunction "2_2") (pintype "passive"))
      (node (ref "J66") (pin "3") (pinfunction "3_3") (pintype "passive"))
      (node (ref "J66") (pin "4") (pinfunction "4_4") (pintype "passive"))
      (node (ref "J66") (pin "5") (pinfunction "5_5") (pintype "passive"))
      (node (ref "J66") (pin "6") (pinfunction "6_6") (pintype "passive"))
      (node (ref "J66") (pin "7") (pinfunction "7_7") (pintype "passive"))
    )
    (net (code "67") (name "Net-(J67-Pad1)") (class "Default")
      (node (ref "J67") (pin "1") (pinfunction "1_1") (pintype "passive"))
      (node (ref "J67") (pin "2") (pinfunction "2_2") (pintype "passive"))
      (node (ref "J67") (pin "3") (pinfunction "3_3") (pintype "passive"))
      (node (ref "J67") (pin "4") (pinfunction "4_4") (pintype "passive"))
      (node (ref "J67") (pin "5") (pinfunction "5_5") (pintype "passive"))
      (node (ref "J67") (pin "6") (pinfunction "6_6") (pintype "passive"))
      (node (ref "J67") (pin "7") (pinfunction "7_7") (pintype "passive"))
    )
    (net (code "68") (name "Net-(J68-Pad1)") (class "Default")
      (node (ref "J68") (pin "1") (pinfunction "1_1") (pintype "passive"))
      (node (ref "J68") (pin "2") (pinfunction "2_2") (pintype "passive"))
      (node (ref "J68") (pin "3") (pinfunction "3_3") (pintype "passive"))
      (node (ref "J68") (pin "4") (pinfunction "4_4") (pintype "passive"))
      (node (ref "J68") (pin "5") (pinfunction "5_5") (pintype "passive"))
      (node (ref "J68") (pin "6") (pinfunction "6_6") (pintype "passive"))
      (node (ref "J68") (pin "7") (pinfunction "7_7") (pintype "passive"))
    )
    (net (code "69") (name "Net-(J69-Pad1)") (class "Default")
      (node (ref "J69") (pin "1") (pinfunction "1_1") (pintype "passive"))
      (node (ref "J69") (pin "2") (pinfunction "2_2") (pintype "passive"))
      (node (ref "J69") (pin "3") (pinfunction "3_3") (pintype "passive"))
      (node (ref "J69") (pin "4") (pinfunction "4_4") (pintype "passive"))
      (node (ref "J69") (pin "5") (pinfunction "5_5") (pintype "passive"))
      (node (ref "J69") (pin "6") (pinfunction "6_6") (pintype "passive"))
      (node (ref "J69") (pin "7") (pinfunction "7_7") (pintype "passive"))
    )
    (net (code "70") (name "Net-(J70-Pad1)") (class "Default")
      (node (ref "J70") (pin "1") (pinfunction "1_1") (pintype "passive"))
      (node (ref "J70") (pin "2") (pinfunction "2_2") (pintype "passive"))
      (node (ref "J70") (pin "3") (pinfunction "3_3") (pintype "passive"))
      (node (ref "J70") (pin "4") (pinfunction "4_4") (pintype "passive"))
      (node (ref "J70") (pin "5") (pinfunction "5_5") (pintype "passive"))
      (node (ref "J70") (pin "6") (pinfunction "6_6") (pintype "passive"))
      (node (ref "J70") (pin "7") (pinfunction "7_7") (pintype "passive"))
    )
    (net (code "71") (name "Net-(J71-Pad1)") (class "Default")
      (node (ref "J71") (pin "1") (pinfunction "1_1") (pintype "passive"))
      (node (ref "J71") (pin "2") (pinfunction "2_2") (pintype "passive"))
      (node (ref "J71") (pin "3") (pinfunction "3_3") (pintype "passive"))
      (node (ref "J71") (pin "4") (pinfunction "4_4") (pintype "passive"))
      (node (ref "J71") (pin "5") (pinfunction "5_5") (pintype "passive"))
      (node (ref "J71") (pin "6") (pinfunction "6_6") (pintype "passive"))
      (node (ref "J71") (pin "7") (pinfunction "7_7") (pintype "passive"))
    )
    (net (code "72") (name "Net-(J72-Pad1)") (class "Default")
      (node (ref "J72") (pin "1") (pinfunction "1_1") (pintype "passive"))
      (node (ref "J72") (pin "2") (pinfunction "2_2") (pintype "passive"))
      (node (ref "J72") (pin "3") (pinfunction "3_3") (pintype "passive"))
      (node (ref "J72") (pin "4") (pinfunction "4_4") (pintype "passive"))
      (node (ref "J72") (pin "5") (pinfunction "5_5") (pintype "passive"))
      (node (ref "J72") (pin "6") (pinfunction "6_6") (pintype "passive"))
      (node (ref "J72") (pin "7") (pinfunction "7_7") (pintype "passive"))
    )
    (net (code "73") (name "Net-(J73-Pad1)") (class "Default")
      (node (ref "J73") (pin "1") (pinfunction "1_1") (pintype "passive"))
      (node (ref "J73") (pin "2") (pinfunction "2_2") (pintype "passive"))
      (node (ref "J73") (pin "3") (pinfunction "3_3") (pintype "passive"))
      (node (ref "J73") (pin "4") (pinfunction "4_4") (pintype "passive"))
      (node (ref "J73") (pin "5") (pinfunction "5_5") (pintype "passive"))
      (node (ref "J73") (pin "6") (pinfunction "6_6") (pintype "passive"))
      (node (ref "J73") (pin "7") (pinfunction "7_7") (pintype "passive"))
    )
    (net (code "74") (name "Net-(J74-Pad1)") (class "Default")
      (node (ref "J74") (pin "1") (pinfunction "1_1") (pintype "passive"))
      (node (ref "J74") (pin "2") (pinfunction "2_2") (pintype "passive"))
      (node (ref "J74") (pin "3") (pinfunction "3_3") (pintype "passive"))
      (node (ref "J74") (pin "4") (pinfunction "4_4") (pintype "passive"))
      (node (ref "J74") (pin "5") (pinfunction "5_5") (pintype "passive"))
      (node (ref "J74") (pin "6") (pinfunction "6_6") (pintype "passive"))
      (node (ref "J74") (pin "7") (pinfunction "7_7") (pintype "passive"))
    )
    (net (code "75") (name "Net-(J75-Pad1)") (class "Default")
      (node (ref "J75") (pin "1") (pinfunction "1_1") (pintype "passive"))
      (node (ref "J75") (pin "2") (pinfunction "2_2") (pintype "passive"))
      (node (ref "J75") (pin "3") (pinfunction "3_3") (pintype "passive"))
      (node (ref "J75") (pin "4") (pinfunction "4_4") (pintype "passive"))
      (node (ref "J75") (pin "5") (pinfunction "5_5") (pintype "passive"))
      (node (ref "J75") (pin "6") (pinfunction "6_6") (pintype "passive"))
      (node (ref "J75") (pin "7") (pinfunction "7_7") (pintype "passive"))
    )
    (net (code "76") (name "Net-(J76-Pad1)") (class "Default")
      (node (ref "J76") (pin "1") (pinfunction "1_1") (pintype "passive"))
      (node (ref "J76") (pin "2") (pinfunction "2_2") (pintype "passive"))
      (node (ref "J76") (pin "3") (pinfunction "3_3") (pintype "passive"))
      (node (ref "J76") (pin "4") (pinfunction "4_4") (pintype "passive"))
      (node (ref "J76") (pin "5") (pinfunction "5_5") (pintype "passive"))
      (node (ref "J76") (pin "6") (pinfunction "6_6") (pintype "passive"))
      (node (ref "J76") (pin "7") (pinfunction "7_7") (pintype "passive"))
    )
    (net (code "77") (name "Net-(J77-Pad1)") (class "Default")
      (node (ref "J77") (pin "1") (pinfunction "1_1") (pintype "passive"))
      (node (ref "J77") (pin "2") (pinfunction "2_2") (pintype "passive"))
      (node (ref "J77") (pin "3") (pinfunction "3_3") (pintype "passive"))
      (node (ref "J77") (pin "4") (pinfunction "4_4") (pintype "passive"))
      (node (ref "J77") (pin "5") (pinfunction "5_5") (pintype "passive"))
      (node (ref "J77") (pin "6") (pinfunction "6_6") (pintype "passive"))
      (node (ref "J77") (pin "7") (pinfunction "7_7") (pintype "passive"))
    )
    (net (code "78") (name "Net-(J78-Pad1)") (class "Default")
      (node (ref "J78") (pin "1") (pinfunction "1_1") (pintype "passive"))
      (node (ref "J78") (pin "2") (pinfunction "2_2") (pintype "passive"))
      (node (ref "J78") (pin "3") (pinfunction "3_3") (pintype "passive"))
      (node (ref "J78") (pin "4") (pinfunction "4_4") (pintype "passive"))
      (node (ref "J78") (pin "5") (pinfunction "5_5") (pintype "passive"))
      (node (ref "J78") (pin "6") (pinfunction "6_6") (pintype "passive"))
      (node (ref "J78") (pin "7") (pinfunction "7_7") (pintype "passive"))
    )
    (net (code "79") (name "Net-(J79-Pad1)") (class "Default")
      (node (ref "J79") (pin "1") (pinfunction "1_1") (pintype "passive"))
      (node (ref "J79") (pin "2") (pinfunction "2_2") (pintype "passive"))
      (node (ref "J79") (pin "3") (pinfunction "3_3") (pintype "passive"))
      (node (ref "J79") (pin "4") (pinfunction "4_4") (pintype "passive"))
      (node (ref "J79") (pin "5") (pinfunction "5_5") (pintype "passive"))
      (node (ref "J79") (pin "6") (pinfunction "6_6") (pintype "passive"))
      (node (ref "J79") (pin "7") (pinfunction "7_7") (pintype "passive"))
    )
    (net (code "80") (name "Net-(J80-Pad1)") (class "Default")
      (node (ref "J80") (pin "1") (pinfunction "1_1") (pintype "passive"))
      (node (ref "J80") (pin "2") (pinfunction "2_2") (pintype "passive"))
      (node (ref "J80") (pin "3") (pinfunction "3_3") (pintype "passive"))
      (node (ref "J80") (pin "4") (pinfunction "4_4") (pintype "passive"))
      (node (ref "J80") (pin "5") (pinfunction "5_5") (pintype "passive"))
      (node (ref "J80") (pin "6") (pinfunction "6_6") (pintype "passive"))
      (node (ref "J80") (pin "7") (pinfunction "7_7") (pintype "passive"))
    )
    (net (code "81") (name "Net-(J81-Pad1)") (class "Default")
      (node (ref "J81") (pin "1") (pinfunction "1_1") (pintype "passive"))
      (node (ref "J81") (pin "2") (pinfunction "2_2") (pintype "passive"))
      (node (ref "J81") (pin "3") (pinfunction "3_3") (pintype "passive"))
      (node (ref "J81") (pin "4") (pinfunction "4_4") (pintype "passive"))
      (node (ref "J81") (pin "5") (pinfunction "5_5") (pintype "passive"))
      (node (ref "J81") (pin "6") (pinfunction "6_6") (pintype "passive"))
      (node (ref "J81") (pin "7") (pinfunction "7_7") (pintype "passive"))
    )
    (net (code "82") (name "Net-(J82-Pad1)") (class "Default")
      (node (ref "J82") (pin "1") (pinfunction "1_1") (pintype "passive"))
      (node (ref "J82") (pin "2") (pinfunction "2_2") (pintype "passive"))
      (node (ref "J82") (pin "3") (pinfunction "3_3") (pintype "passive"))
      (node (ref "J82") (pin "4") (pinfunction "4_4") (pintype "passive"))
      (node (ref "J82") (pin "5") (pinfunction "5_5") (pintype "passive"))
      (node (ref "J82") (pin "6") (pinfunction "6_6") (pintype "passive"))
      (node (ref "J82") (pin "7") (pinfunction "7_7") (pintype "passive"))
    )
    (net (code "83") (name "Net-(J83-Pad1)") (class "Default")
      (node (ref "J83") (pin "1") (pinfunction "1_1") (pintype "passive"))
      (node (ref "J83") (pin "2") (pinfunction "2_2") (pintype "passive"))
      (node (ref "J83") (pin "3") (pinfunction "3_3") (pintype "passive"))
      (node (ref "J83") (pin "4") (pinfunction "4_4") (pintype "passive"))
      (node (ref "J83") (pin "5") (pinfunction "5_5") (pintype "passive"))
      (node (ref "J83") (pin "6") (pinfunction "6_6") (pintype "passive"))
      (node (ref "J83") (pin "7") (pinfunction "7_7") (pintype "passive"))
    )
    (net (code "84") (name "Net-(J84-Pad1)") (class "Default")
      (node (ref "J84") (pin "1") (pinfunction "1_1") (pintype "passive"))
      (node (ref "J84") (pin "2") (pinfunction "2_2") (pintype "passive"))
      (node (ref "J84") (pin "3") (pinfunction "3_3") (pintype "passive"))
      (node (ref "J84") (pin "4") (pinfunction "4_4") (pintype "passive"))
      (node (ref "J84") (pin "5") (pinfunction "5_5") (pintype "passive"))
      (node (ref "J84") (pin "6") (pinfunction "6_6") (pintype "passive"))
      (node (ref "J84") (pin "7") (pinfunction "7_7") (pintype "passive"))
    )
    (net (code "85") (name "Net-(J85-Pad1)") (class "Default")
      (node (ref "J85") (pin "1") (pinfunction "1_1") (pintype "passive"))
      (node (ref "J85") (pin "2") (pinfunction "2_2") (pintype "passive"))
      (node (ref "J85") (pin "3") (pinfunction "3_3") (pintype "passive"))
      (node (ref "J85") (pin "4") (pinfunction "4_4") (pintype "passive"))
      (node (ref "J85") (pin "5") (pinfunction "5_5") (pintype "passive"))
      (node (ref "J85") (pin "6") (pinfunction "6_6") (pintype "passive"))
      (node (ref "J85") (pin "7") (pinfunction "7_7") (pintype "passive"))
    )
    (net (code "86") (name "Net-(J86-Pad1)") (class "Default")
      (node (ref "J86") (pin "1") (pinfunction "1_1") (pintype "passive"))
      (node (ref "J86") (pin "2") (pinfunction "2_2") (pintype "passive"))
      (node (ref "J86") (pin "3") (pinfunction "3_3") (pintype "passive"))
      (node (ref "J86") (pin "4") (pinfunction "4_4") (pintype "passive"))
      (node (ref "J86") (pin "5") (pinfunction "5_5") (pintype "passive"))
      (node (ref "J86") (pin "6") (pinfunction "6_6") (pintype "passive"))
      (node (ref "J86") (pin "7") (pinfunction "7_7") (pintype "passive"))
    )
    (net (code "87") (name "Net-(J87-Pad1)") (class "Default")
      (node (ref "J87") (pin "1") (pinfunction "1_1") (pintype "passive"))
      (node (ref "J87") (pin "2") (pinfunction "2_2") (pintype "passive"))
      (node (ref "J87") (pin "3") (pinfunction "3_3") (pintype "passive"))
      (node (ref "J87") (pin "4") (pinfunction "4_4") (pintype "passive"))
      (node (ref "J87") (pin "5") (pinfunction "5_5") (pintype "passive"))
      (node (ref "J87") (pin "6") (pinfunction "6_6") (pintype "passive"))
      (node (ref "J87") (pin "7") (pinfunction "7_7") (pintype "passive"))
    )
    (net (code "88") (name "Net-(J88-Pad1)") (class "Default")
      (node (ref "J88") (pin "1") (pinfunction "1_1") (pintype "passive"))
      (node (ref "J88") (pin "2") (pinfunction "2_2") (pintype "passive"))
      (node (ref "J88") (pin "3") (pinfunction "3_3") (pintype "passive"))
      (node (ref "J88") (pin "4") (pinfunction "4_4") (pintype "passive"))
      (node (ref "J88") (pin "5") (pinfunction "5_5") (pintype "passive"))
      (node (ref "J88") (pin "6") (pinfunction "6_6") (pintype "passive"))
      (node (ref "J88") (pin "7") (pinfunction "7_7") (pintype "passive"))
    )
    (net (code "89") (name "Net-(J89-Pad1)") (class "Default")
      (node (ref "J89") (pin "1") (pinfunction "1_1") (pintype "passive"))
      (node (ref "J89") (pin "2") (pinfunction "2_2") (pintype "passive"))
      (node (ref "J89") (pin "3") (pinfunction "3_3") (pintype "passive"))
      (node (ref "J89") (pin "4") (pinfunction "4_4") (pintype "passive"))
    )
    (net (code "90") (name "Net-(JP2-1)") (class "Default")
      (node (ref "JP10") (pin "1") (pinfunction "1_1") (pintype "passive"))
      (node (ref "JP2") (pin "P$1") (pinfunction "1_P$1") (pintype "passive"))
    )
    (net (code "91") (name "Net-(JP3-1)") (class "Default")
      (node (ref "JP11") (pin "1") (pinfunction "1_1") (pintype "passive"))
      (node (ref "JP3") (pin "P$1") (pinfunction "1_P$1") (pintype "passive"))
    )
    (net (code "92") (name "Net-(JP4-1)") (class "Default")
      (node (ref "JP12") (pin "1") (pinfunction "1_1") (pintype "passive"))
      (node (ref "JP4") (pin "P$1") (pinfunction "1_P$1") (pintype "passive"))
    )
    (net (code "93") (name "Net-(JP5-1)") (class "Default")
      (node (ref "JP13") (pin "1") (pinfunction "1_1") (pintype "passive"))
      (node (ref "JP5") (pin "P$1") (pinfunction "1_P$1") (pintype "passive"))
    )
    (net (code "94") (name "Net-(JP6-1)") (class "Default")
      (node (ref "JP14") (pin "1") (pinfunction "1_1") (pintype "passive"))
      (node (ref "JP6") (pin "P$1") (pinfunction "1_P$1") (pintype "passive"))
    )
    (net (code "95") (name "Net-(JP7-1)") (class "Default")
      (node (ref "JP15") (pin "1") (pinfunction "1_1") (pintype "passive"))
      (node (ref "JP7") (pin "P$1") (pinfunction "1_P$1") (pintype "passive"))
    )
    (net (code "96") (name "Net-(JP8-1)") (class "Default")
      (node (ref "JP16") (pin "1") (pinfunction "1_1") (pintype "passive"))
      (node (ref "JP8") (pin "P$1") (pinfunction "1_P$1") (pintype "passive"))
    )
    (net (code "97") (name "Net-(JP9-1)") (class "Default")
      (node (ref "JP17") (pin "1") (pinfunction "1_1") (pintype "passive"))
      (node (ref "JP9") (pin "P$1") (pinfunction "1_P$1") (pintype "passive"))
    )
    (net (code "98") (name "VCC") (class "Default")
      (node (ref "DC") (pin "1") (pinfunction "VIN_1") (pintype "passive"))
      (node (ref "J1") (pin "1") (pinfunction "1_1") (pintype "passive"))
      (node (ref "U1") (pin "1") (pinfunction "IN_1") (pintype "input"))
      (node (ref "U1") (pin "3") (pinfunction "EN_3") (pintype "input"))
      (node (ref "X1") (pin "VBUS") (pinfunction "VBUS_VBUS") (pintype "power_in"))
    )
    (net (code "99") (name "VDD") (class "Default")
      (node (ref "DC") (pin "3") (pinfunction "VOUT_3") (pintype "passive"))
      (node (ref "J90") (pin "1") (pinfunction "1_1") (pintype "passive"))
      (node (ref "J90") (pin "10") (pinfunction "10_10") (pintype "passive"))
      (node (ref "J90") (pin "11") (pinfunction "11_11") (pintype "passive"))
      (node (ref "J90") (pin "12") (pinfunction "12_12") (pintype "passive"))
      (node (ref "J90") (pin "13") (pinfunction "13_13") (pintype "passive"))
      (node (ref "J90") (pin "14") (pinfunction "14_14") (pintype "passive"))
      (node (ref "J90") (pin "15") (pinfunction "15_15") (pintype "passive"))
      (node (ref "J90") (pin "16") (pinfunction "16_16") (pintype "passive"))
      (node (ref "J90") (pin "17") (pinfunction "17_17") (pintype "passive"))
      (node (ref "J90") (pin "18") (pinfunction "18_18") (pintype "passive"))
      (node (ref "J90") (pin "19") (pinfunction "19_19") (pintype "passive"))
      (node (ref "J90") (pin "2") (pinfunction "2_2") (pintype "passive"))
      (node (ref "J90") (pin "20") (pinfunction "20_20") (pintype "passive"))
      (node (ref "J90") (pin "3") (pinfunction "3_3") (pintype "passive"))
      (node (ref "J90") (pin "4") (pinfunction "4_4") (pintype "passive"))
      (node (ref "J90") (pin "5") (pinfunction "5_5") (pintype "passive"))
      (node (ref "J90") (pin "6") (pinfunction "6_6") (pintype "passive"))
      (node (ref "J90") (pin "7") (pinfunction "7_7") (pintype "passive"))
      (node (ref "J90") (pin "8") (pinfunction "8_8") (pintype "passive"))
      (node (ref "J90") (pin "9") (pinfunction "9_9") (pintype "passive"))
      (node (ref "J93") (pin "1") (pinfunction "1_1") (pintype "passive"))
      (node (ref "J93") (pin "10") (pinfunction "10_10") (pintype "passive"))
      (node (ref "J93") (pin "11") (pinfunction "11_11") (pintype "passive"))
      (node (ref "J93") (pin "12") (pinfunction "12_12") (pintype "passive"))
      (node (ref "J93") (pin "13") (pinfunction "13_13") (pintype "passive"))
      (node (ref "J93") (pin "14") (pinfunction "14_14") (pintype "passive"))
      (node (ref "J93") (pin "15") (pinfunction "15_15") (pintype "passive"))
      (node (ref "J93") (pin "16") (pinfunction "16_16") (pintype "passive"))
      (node (ref "J93") (pin "17") (pinfunction "17_17") (pintype "passive"))
      (node (ref "J93") (pin "18") (pinfunction "18_18") (pintype "passive"))
      (node (ref "J93") (pin "19") (pinfunction "19_19") (pintype "passive"))
      (node (ref "J93") (pin "2") (pinfunction "2_2") (pintype "passive"))
      (node (ref "J93") (pin "20") (pinfunction "20_20") (pintype "passive"))
      (node (ref "J93") (pin "3") (pinfunction "3_3") (pintype "passive"))
      (node (ref "J93") (pin "4") (pinfunction "4_4") (pintype "passive"))
      (node (ref "J93") (pin "5") (pinfunction "5_5") (pintype "passive"))
      (node (ref "J93") (pin "6") (pinfunction "6_6") (pintype "passive"))
      (node (ref "J93") (pin "7") (pinfunction "7_7") (pintype "passive"))
      (node (ref "J93") (pin "8") (pinfunction "8_8") (pintype "passive"))
      (node (ref "J93") (pin "9") (pinfunction "9_9") (pintype "passive"))
      (node (ref "JP18") (pin "1") (pinfunction "1_1") (pintype "passive"))
      (node (ref "JP19") (pin "1") (pinfunction "1_1") (pintype "passive"))
      (node (ref "JP22") (pin "1") (pinfunction "1_1") (pintype "passive"))
      (node (ref "JP25") (pin "1") (pinfunction "1_1") (pintype "passive"))
      (node (ref "U1") (pin "5") (pinfunction "OUT_5") (pintype "passive"))
    )
    (net (code "100") (name "unconnected-(U1-BP-Pad4)") (class "Default")
      (node (ref "U1") (pin "4") (pinfunction "BP_4") (pintype "input"))
    )
    (net (code "101") (name "unconnected-(X1-PadD+)") (class "Default")
      (node (ref "X1") (pin "D+") (pinfunction "D+_D+") (pintype "bidirectional"))
    )
    (net (code "102") (name "unconnected-(X1-PadD-)") (class "Default")
      (node (ref "X1") (pin "D-") (pinfunction "D-_D-") (pintype "bidirectional"))
    )
    (net (code "103") (name "unconnected-(X1-PadID)") (class "Default")
      (node (ref "X1") (pin "ID") (pinfunction "ID_ID") (pintype "bidirectional"))
    )
  )
)
